# 2018_FDP_ACTIONNEUR.net
KiCad netlist of a schematic drawn in Altium Designer
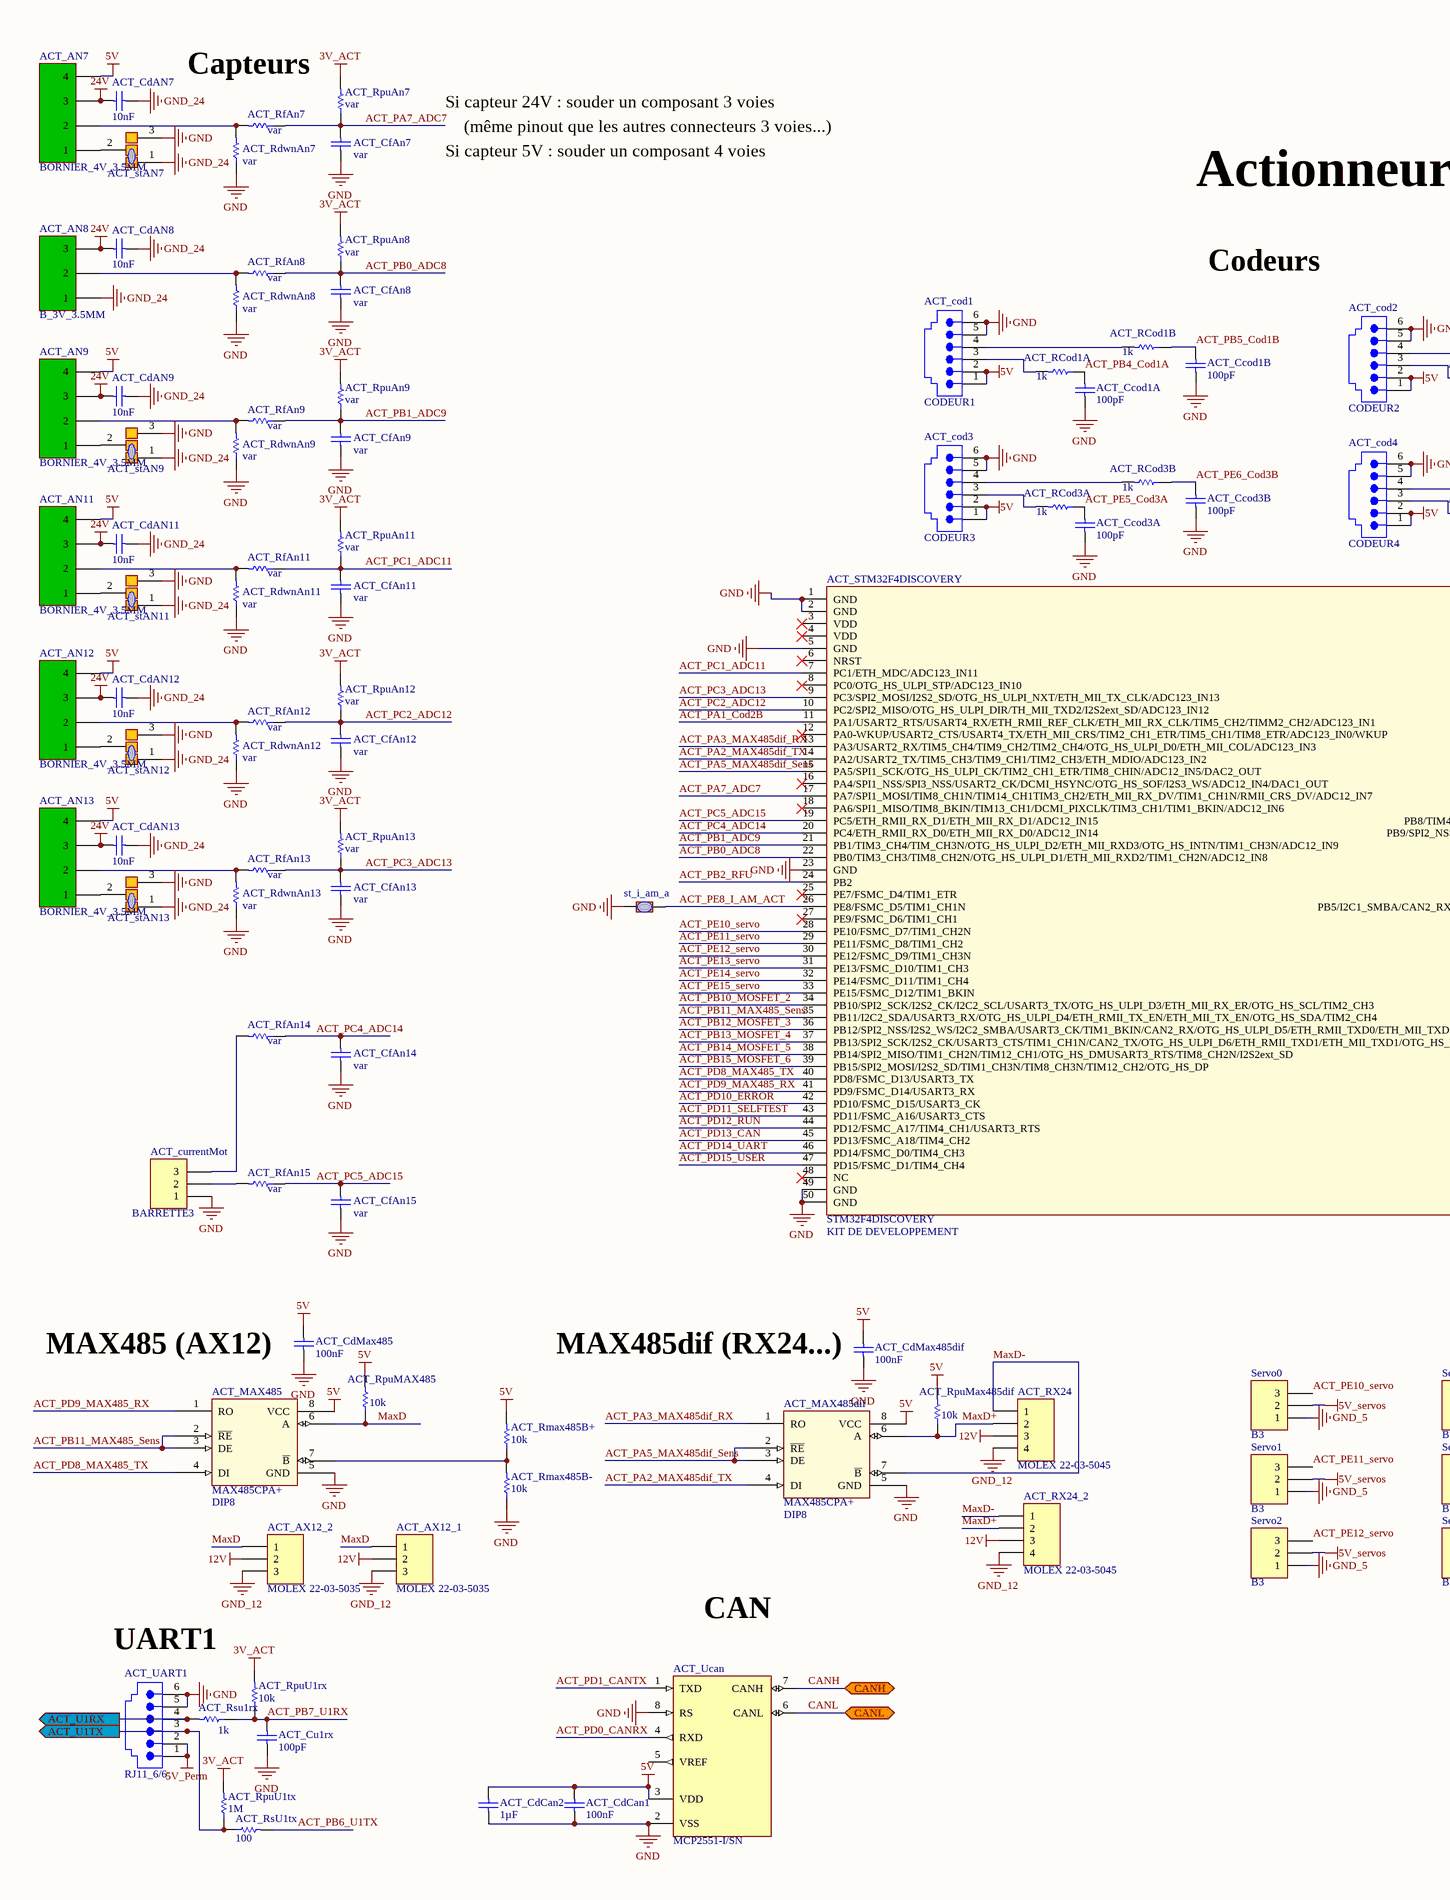
[diagram p0: 2018_FDP_ACTIONNEUR.SchDoc, left]
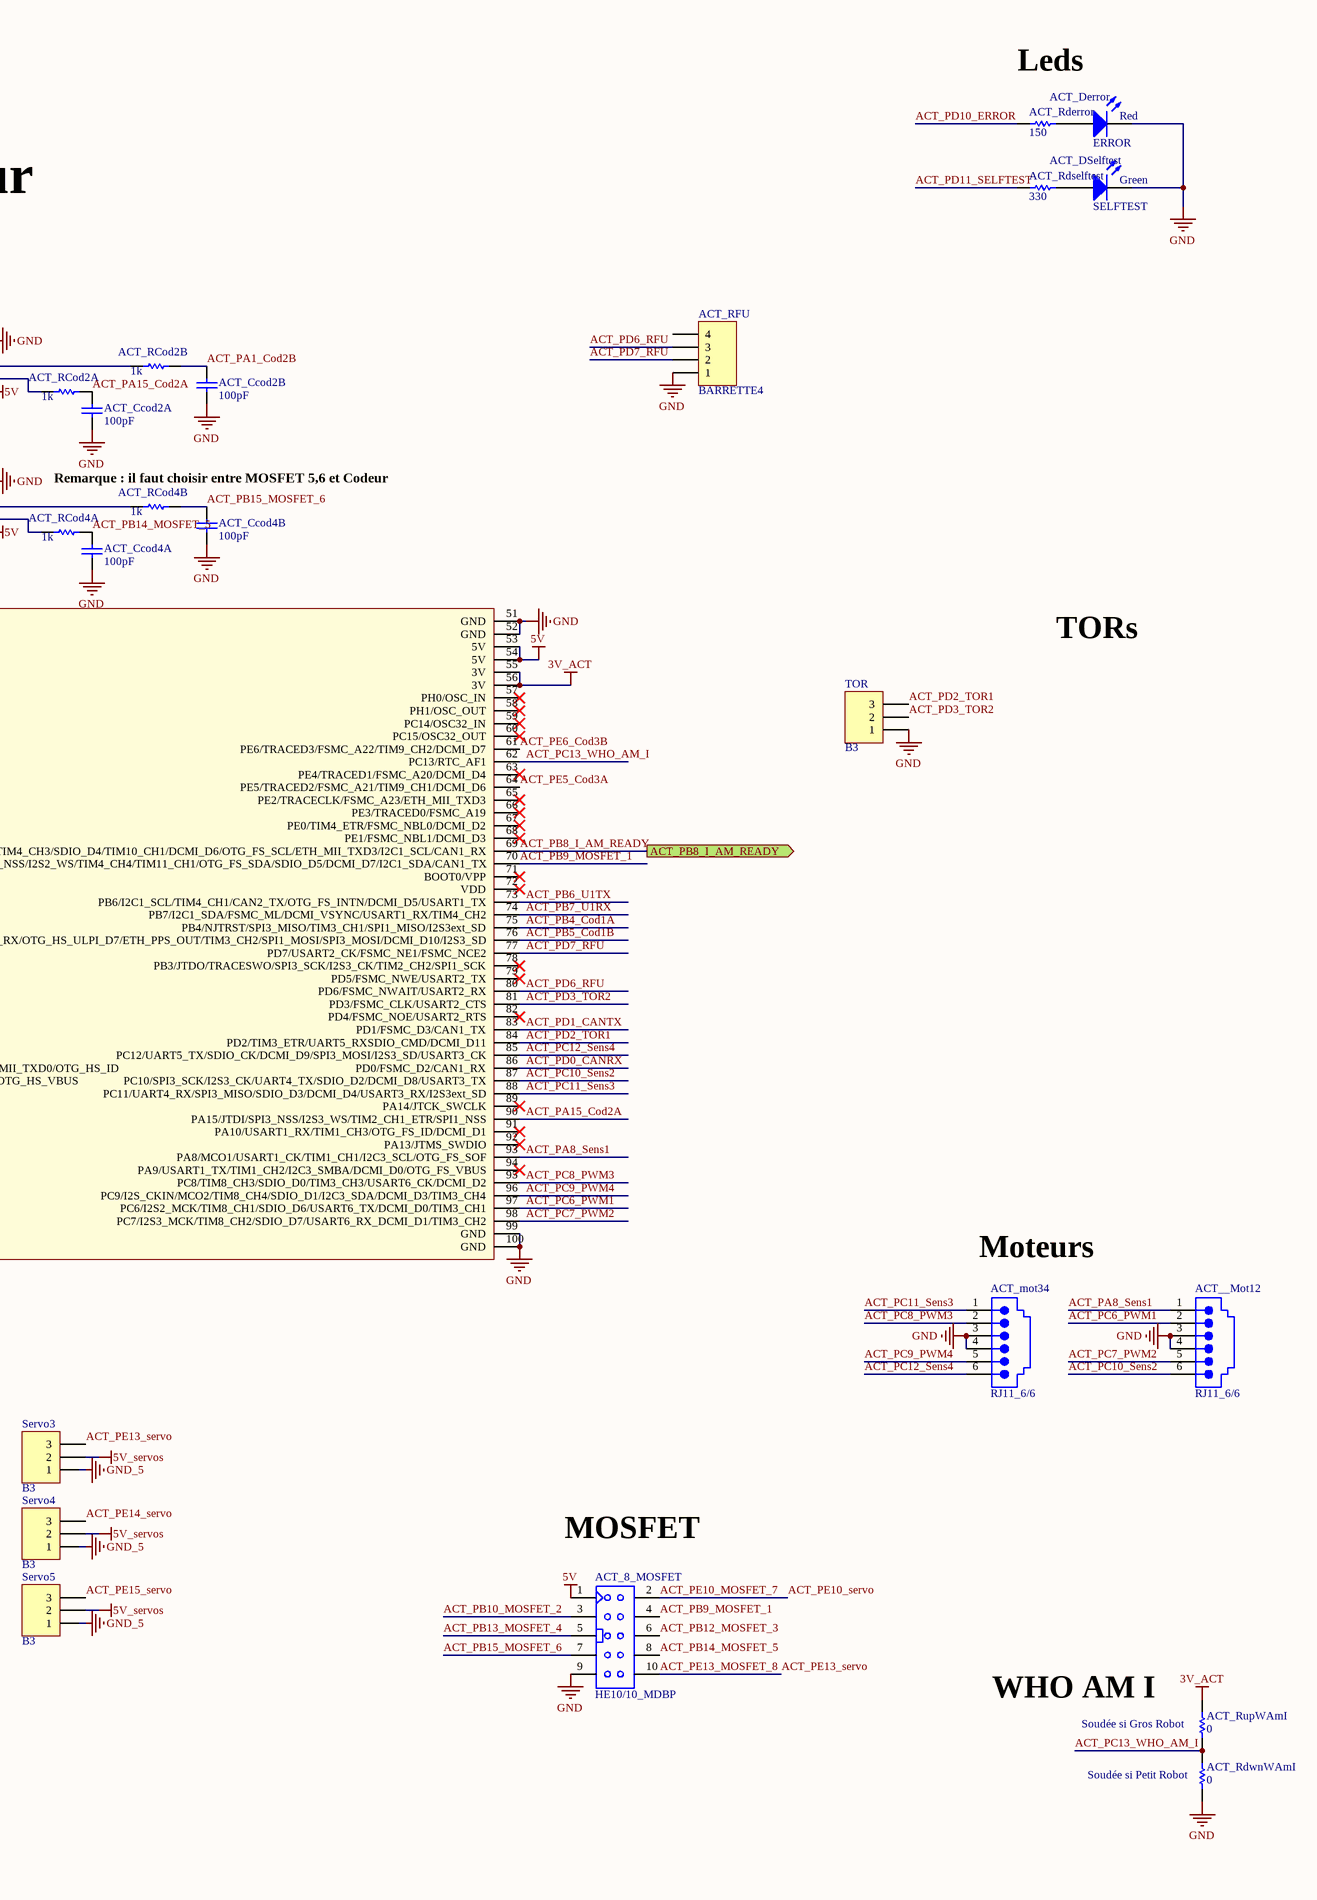
[diagram p1: 2018_FDP_ACTIONNEUR.SchDoc, right]

(export (version "E")
  (design (tool "Eeschema 10.0.6"))
  (components
    (comp (ref "ACT_8_MOSFET")
      (value "HE10/10_MALE_DROIT_BAS_PROFIL")
      (footprint "HE10/10_M_D_BP")
      (description "EMBASE HE10/10 MALE DROIT BAS PROFIL")
      (fields (field (name "TYPE") "HE10/10_MDBP"))
      (libsource (lib "connecteurs") (part "HE10/10_MALE_DROIT_BAS_PROFIL"))
    )
    (comp (ref "ACT_AN7")
      (value "BORNIER_4V_3.5MM")
      (footprint "BORNIER_4V_3.5MM")
      (libsource (lib "Connecteur") (part "BORNIER_4V_3.5MM"))
    )
    (comp (ref "ACT_AN8")
      (value "B_3V_3.5MM")
      (footprint "BORNIER_3V_3.5MM")
      (libsource (lib "Connecteur") (part "BORNIER_3V_3.5MM"))
    )
    (comp (ref "ACT_AN9")
      (value "BORNIER_4V_3.5MM")
      (footprint "BORNIER_4V_3.5MM")
      (libsource (lib "Connecteur") (part "BORNIER_4V_3.5MM"))
    )
    (comp (ref "ACT_AN11")
      (value "BORNIER_4V_3.5MM")
      (footprint "BORNIER_4V_3.5MM")
      (libsource (lib "Connecteur") (part "BORNIER_4V_3.5MM"))
    )
    (comp (ref "ACT_AN12")
      (value "BORNIER_4V_3.5MM")
      (footprint "BORNIER_4V_3.5MM")
      (libsource (lib "Connecteur") (part "BORNIER_4V_3.5MM"))
    )
    (comp (ref "ACT_AN13")
      (value "BORNIER_4V_3.5MM")
      (footprint "BORNIER_4V_3.5MM")
      (libsource (lib "Connecteur") (part "BORNIER_4V_3.5MM"))
    )
    (comp (ref "ACT_AX12_1")
      (value "MOLEX 22-03-5035")
      (footprint "MOLEX3_2.5MM")
      (description "Header, 3-Pin")
      (fields (field (name "PUBLISHER") "Altium Limited"))
      (libsource (lib "") (part "BARRETTE3_1"))
    )
    (comp (ref "ACT_AX12_2")
      (value "MOLEX 22-03-5035")
      (footprint "MOLEX3_2.5MM")
      (description "Header, 3-Pin")
      (fields (field (name "PUBLISHER") "Altium Limited"))
      (libsource (lib "") (part "BARRETTE3_1"))
    )
    (comp (ref "ACT_Ccod1A")
      (value "100pF")
      (footprint "C0805_N")
      (description "Capacitor")
      (fields (field (name "PUBLISHER") "Altium Limited"))
      (libsource (lib "_ROBOT") (part "Condensateur"))
    )
    (comp (ref "ACT_Ccod1B")
      (value "100pF")
      (footprint "C0805_N")
      (description "Capacitor")
      (fields (field (name "PUBLISHER") "Altium Limited"))
      (libsource (lib "_ROBOT") (part "Condensateur"))
    )
    (comp (ref "ACT_Ccod2A")
      (value "100pF")
      (footprint "C0805_N")
      (description "Capacitor")
      (fields (field (name "PUBLISHER") "Altium Limited"))
      (libsource (lib "_ROBOT") (part "Condensateur"))
    )
    (comp (ref "ACT_Ccod2B")
      (value "100pF")
      (footprint "C0805_N")
      (description "Capacitor")
      (fields (field (name "PUBLISHER") "Altium Limited"))
      (libsource (lib "_ROBOT") (part "Condensateur"))
    )
    (comp (ref "ACT_Ccod3A")
      (value "100pF")
      (footprint "C0805_N")
      (description "Capacitor")
      (fields (field (name "PUBLISHER") "Altium Limited"))
      (libsource (lib "_ROBOT") (part "Condensateur"))
    )
    (comp (ref "ACT_Ccod3B")
      (value "100pF")
      (footprint "C0805_N")
      (description "Capacitor")
      (fields (field (name "PUBLISHER") "Altium Limited"))
      (libsource (lib "_ROBOT") (part "Condensateur"))
    )
    (comp (ref "ACT_Ccod4A")
      (value "100pF")
      (footprint "C0805_N")
      (description "Capacitor")
      (fields (field (name "PUBLISHER") "Altium Limited"))
      (libsource (lib "_ROBOT") (part "Condensateur"))
    )
    (comp (ref "ACT_Ccod4B")
      (value "100pF")
      (footprint "C0805_N")
      (description "Capacitor")
      (fields (field (name "PUBLISHER") "Altium Limited"))
      (libsource (lib "_ROBOT") (part "Condensateur"))
    )
    (comp (ref "ACT_CdAN7")
      (value "10nF")
      (footprint "C0805_N")
      (description "Capacitor")
      (fields (field (name "PUBLISHER") "Altium Limited"))
      (libsource (lib "_ROBOT") (part "Condensateur"))
    )
    (comp (ref "ACT_CdAN8")
      (value "10nF")
      (footprint "C0805_N")
      (description "Capacitor")
      (fields (field (name "PUBLISHER") "Altium Limited"))
      (libsource (lib "_ROBOT") (part "Condensateur"))
    )
    (comp (ref "ACT_CdAN9")
      (value "10nF")
      (footprint "C0805_N")
      (description "Capacitor")
      (fields (field (name "PUBLISHER") "Altium Limited"))
      (libsource (lib "_ROBOT") (part "Condensateur"))
    )
    (comp (ref "ACT_CdAN11")
      (value "10nF")
      (footprint "C0805_N")
      (description "Capacitor")
      (fields (field (name "PUBLISHER") "Altium Limited"))
      (libsource (lib "_ROBOT") (part "Condensateur"))
    )
    (comp (ref "ACT_CdAN12")
      (value "10nF")
      (footprint "C0805_N")
      (description "Capacitor")
      (fields (field (name "PUBLISHER") "Altium Limited"))
      (libsource (lib "_ROBOT") (part "Condensateur"))
    )
    (comp (ref "ACT_CdAN13")
      (value "10nF")
      (footprint "C0805_N")
      (description "Capacitor")
      (fields (field (name "PUBLISHER") "Altium Limited"))
      (libsource (lib "_ROBOT") (part "Condensateur"))
    )
    (comp (ref "ACT_CdCan1")
      (value "100nF")
      (footprint "C0805_N")
      (description "Capacitor")
      (fields (field (name "PUBLISHER") "Altium Limited"))
      (libsource (lib "_ROBOT") (part "Condensateur"))
    )
    (comp (ref "ACT_CdCan2")
      (value "1µF")
      (footprint "C0805_N")
      (description "Capacitor")
      (fields (field (name "PUBLISHER") "Altium Limited"))
      (libsource (lib "_ROBOT") (part "Condensateur"))
    )
    (comp (ref "ACT_CdMax485")
      (value "100nF")
      (footprint "C0805_N")
      (description "Capacitor")
      (fields (field (name "PUBLISHER") "Altium Limited"))
      (libsource (lib "_ROBOT") (part "Condensateur"))
    )
    (comp (ref "ACT_CdMax485dif")
      (value "100nF")
      (footprint "C0805_N")
      (description "Capacitor")
      (fields (field (name "PUBLISHER") "Altium Limited"))
      (libsource (lib "_ROBOT") (part "Condensateur"))
    )
    (comp (ref "ACT_CfAn7")
      (value "var")
      (footprint "C0805_N")
      (description "Capacitor")
      (fields (field (name "PUBLISHER") "Altium Limited"))
      (libsource (lib "_ROBOT") (part "Condensateur"))
    )
    (comp (ref "ACT_CfAn8")
      (value "var")
      (footprint "C0805_N")
      (description "Capacitor")
      (fields (field (name "PUBLISHER") "Altium Limited"))
      (libsource (lib "_ROBOT") (part "Condensateur"))
    )
    (comp (ref "ACT_CfAn9")
      (value "var")
      (footprint "C0805_N")
      (description "Capacitor")
      (fields (field (name "PUBLISHER") "Altium Limited"))
      (libsource (lib "_ROBOT") (part "Condensateur"))
    )
    (comp (ref "ACT_CfAn11")
      (value "var")
      (footprint "C0805_N")
      (description "Capacitor")
      (fields (field (name "PUBLISHER") "Altium Limited"))
      (libsource (lib "_ROBOT") (part "Condensateur"))
    )
    (comp (ref "ACT_CfAn12")
      (value "var")
      (footprint "C0805_N")
      (description "Capacitor")
      (fields (field (name "PUBLISHER") "Altium Limited"))
      (libsource (lib "_ROBOT") (part "Condensateur"))
    )
    (comp (ref "ACT_CfAn13")
      (value "var")
      (footprint "C0805_N")
      (description "Capacitor")
      (fields (field (name "PUBLISHER") "Altium Limited"))
      (libsource (lib "_ROBOT") (part "Condensateur"))
    )
    (comp (ref "ACT_CfAn14")
      (value "var")
      (footprint "C0805_N")
      (description "Capacitor")
      (fields (field (name "PUBLISHER") "Altium Limited"))
      (libsource (lib "_ROBOT") (part "Condensateur"))
    )
    (comp (ref "ACT_CfAn15")
      (value "var")
      (footprint "C0805_N")
      (description "Capacitor")
      (fields (field (name "PUBLISHER") "Altium Limited"))
      (libsource (lib "_ROBOT") (part "Condensateur"))
    )
    (comp (ref "ACT_cod1")
      (value "CODEUR1")
      (footprint "RJ11_6/6 - droit")
      (description "Right Angle, Standard Profile, Offset Latch DECconnect, Flangeless PCB Jack")
      (fields (field (name "PUBLISHER") "Altium Limited"))
      (libsource (lib "miniprojet") (part "RJ11_6/6"))
    )
    (comp (ref "ACT_cod2")
      (value "CODEUR2")
      (footprint "RJ11_6/6 - droit")
      (description "Right Angle, Standard Profile, Offset Latch DECconnect, Flangeless PCB Jack")
      (fields (field (name "PUBLISHER") "Altium Limited"))
      (libsource (lib "miniprojet") (part "RJ11_6/6"))
    )
    (comp (ref "ACT_cod3")
      (value "CODEUR3")
      (footprint "RJ11_6/6 - droit")
      (description "Right Angle, Standard Profile, Offset Latch DECconnect, Flangeless PCB Jack")
      (fields (field (name "PUBLISHER") "Altium Limited"))
      (libsource (lib "miniprojet") (part "RJ11_6/6"))
    )
    (comp (ref "ACT_cod4")
      (value "CODEUR4")
      (footprint "RJ11_6/6 - droit")
      (description "Right Angle, Standard Profile, Offset Latch DECconnect, Flangeless PCB Jack")
      (fields (field (name "PUBLISHER") "Altium Limited"))
      (libsource (lib "miniprojet") (part "RJ11_6/6"))
    )
    (comp (ref "ACT_Cu1rx")
      (value "100pF")
      (footprint "C0805_N")
      (description "Capacitor")
      (fields (field (name "PUBLISHER") "Altium Limited"))
      (libsource (lib "_ROBOT") (part "Condensateur"))
    )
    (comp (ref "ACT_currentMot")
      (value "BARRETTE3")
      (footprint "HE14_3")
      (description "Header, 3-Pin")
      (fields (field (name "PUBLISHER") "Altium Limited"))
      (libsource (lib "Connecteur") (part "BARRETTE3"))
    )
    (comp (ref "ACT_Derror")
      (value "ERROR")
      (footprint "LED_0805")
      (description "Typical LED")
      (fields (field (name "PUBLISHER") "Altium Limited"))
      (libsource (lib "_ROBOT") (part "LED"))
    )
    (comp (ref "ACT_DSelftest")
      (value "SELFTEST")
      (footprint "LED_0805")
      (description "Typical LED")
      (fields (field (name "PUBLISHER") "Altium Limited"))
      (libsource (lib "_ROBOT") (part "LED"))
    )
    (comp (ref "ACT_MAX485")
      (value "MAX485CPA+_DIP8")
      (footprint "SO8_N")
      (description "EMETTEUR/RECEPTEUR FAIBLE PUISSANCE DE LIAISONS RS422/RS485 - DIP8")
      (fields (field (name "TYPE") "MAX485CPA+") (field (name "PACKAGE") "DIP8"))
      (libsource (lib "circuits integres") (part "MAX485CPA+_DIP8"))
    )
    (comp (ref "ACT_MAX485dif")
      (value "MAX485CPA+_DIP8")
      (footprint "SO8_N")
      (description "EMETTEUR/RECEPTEUR FAIBLE PUISSANCE DE LIAISONS RS422/RS485 - DIP8")
      (fields (field (name "TYPE") "MAX485CPA+") (field (name "PACKAGE") "DIP8"))
      (libsource (lib "circuits integres") (part "MAX485CPA+_DIP8"))
    )
    (comp (ref "ACT_mot34")
      (value "RJ11_6/6")
      (footprint "RJ11_6/6 - droit")
      (description "Right Angle, Standard Profile, Offset Latch DECconnect, Flangeless PCB Jack")
      (fields (field (name "PUBLISHER") "Altium Limited"))
      (libsource (lib "Connecteur") (part "RJ11_6/6"))
    )
    (comp (ref "ACT_RCod1A")
      (value "1k")
      (footprint "R1206_N")
      (description "Resistor")
      (fields (field (name "PUBLISHER") "Altium Limited"))
      (libsource (lib "_ROBOT") (part "Resistor"))
    )
    (comp (ref "ACT_RCod1B")
      (value "1k")
      (footprint "R1206_N")
      (description "Resistor")
      (fields (field (name "PUBLISHER") "Altium Limited"))
      (libsource (lib "_ROBOT") (part "Resistor"))
    )
    (comp (ref "ACT_RCod2A")
      (value "1k")
      (footprint "R1206_N")
      (description "Resistor")
      (fields (field (name "PUBLISHER") "Altium Limited"))
      (libsource (lib "_ROBOT") (part "Resistor"))
    )
    (comp (ref "ACT_RCod2B")
      (value "1k")
      (footprint "R1206_N")
      (description "Resistor")
      (fields (field (name "PUBLISHER") "Altium Limited"))
      (libsource (lib "_ROBOT") (part "Resistor"))
    )
    (comp (ref "ACT_RCod3A")
      (value "1k")
      (footprint "R1206_N")
      (description "Resistor")
      (fields (field (name "PUBLISHER") "Altium Limited"))
      (libsource (lib "_ROBOT") (part "Resistor"))
    )
    (comp (ref "ACT_RCod3B")
      (value "1k")
      (footprint "R1206_N")
      (description "Resistor")
      (fields (field (name "PUBLISHER") "Altium Limited"))
      (libsource (lib "_ROBOT") (part "Resistor"))
    )
    (comp (ref "ACT_RCod4A")
      (value "1k")
      (footprint "R1206_N")
      (description "Resistor")
      (fields (field (name "PUBLISHER") "Altium Limited"))
      (libsource (lib "_ROBOT") (part "Resistor"))
    )
    (comp (ref "ACT_RCod4B")
      (value "1k")
      (footprint "R1206_N")
      (description "Resistor")
      (fields (field (name "PUBLISHER") "Altium Limited"))
      (libsource (lib "_ROBOT") (part "Resistor"))
    )
    (comp (ref "ACT_Rderror")
      (value "150")
      (footprint "R1206_N")
      (description "Resistor")
      (fields (field (name "PUBLISHER") "Altium Limited"))
      (libsource (lib "_ROBOT") (part "Resistor"))
    )
    (comp (ref "ACT_Rdselftest")
      (value "330")
      (footprint "R1206_N")
      (description "Resistor")
      (fields (field (name "PUBLISHER") "Altium Limited"))
      (libsource (lib "_ROBOT") (part "Resistor"))
    )
    (comp (ref "ACT_RdwnAn7")
      (value "var")
      (footprint "R1206_N")
      (description "Resistor")
      (fields (field (name "PUBLISHER") "Altium Limited"))
      (libsource (lib "_ROBOT") (part "Resistor"))
    )
    (comp (ref "ACT_RdwnAn8")
      (value "var")
      (footprint "R1206_N")
      (description "Resistor")
      (fields (field (name "PUBLISHER") "Altium Limited"))
      (libsource (lib "_ROBOT") (part "Resistor"))
    )
    (comp (ref "ACT_RdwnAn9")
      (value "var")
      (footprint "R1206_N")
      (description "Resistor")
      (fields (field (name "PUBLISHER") "Altium Limited"))
      (libsource (lib "_ROBOT") (part "Resistor"))
    )
    (comp (ref "ACT_RdwnAn11")
      (value "var")
      (footprint "R1206_N")
      (description "Resistor")
      (fields (field (name "PUBLISHER") "Altium Limited"))
      (libsource (lib "_ROBOT") (part "Resistor"))
    )
    (comp (ref "ACT_RdwnAn12")
      (value "var")
      (footprint "R1206_N")
      (description "Resistor")
      (fields (field (name "PUBLISHER") "Altium Limited"))
      (libsource (lib "_ROBOT") (part "Resistor"))
    )
    (comp (ref "ACT_RdwnAn13")
      (value "var")
      (footprint "R1206_N")
      (description "Resistor")
      (fields (field (name "PUBLISHER") "Altium Limited"))
      (libsource (lib "_ROBOT") (part "Resistor"))
    )
    (comp (ref "ACT_RdwnWAmI")
      (value "0")
      (footprint "R1206_N")
      (description "Resistor")
      (fields (field (name "PUBLISHER") "Altium Limited"))
      (libsource (lib "_ROBOT") (part "Resistor"))
    )
    (comp (ref "ACT_RfAn7")
      (value "var")
      (footprint "R1206_N")
      (description "Resistor")
      (fields (field (name "PUBLISHER") "Altium Limited"))
      (libsource (lib "_ROBOT") (part "Resistor"))
    )
    (comp (ref "ACT_RfAn8")
      (value "var")
      (footprint "R1206_N")
      (description "Resistor")
      (fields (field (name "PUBLISHER") "Altium Limited"))
      (libsource (lib "_ROBOT") (part "Resistor"))
    )
    (comp (ref "ACT_RfAn9")
      (value "var")
      (footprint "R1206_N")
      (description "Resistor")
      (fields (field (name "PUBLISHER") "Altium Limited"))
      (libsource (lib "_ROBOT") (part "Resistor"))
    )
    (comp (ref "ACT_RfAn11")
      (value "var")
      (footprint "R1206_N")
      (description "Resistor")
      (fields (field (name "PUBLISHER") "Altium Limited"))
      (libsource (lib "_ROBOT") (part "Resistor"))
    )
    (comp (ref "ACT_RfAn12")
      (value "var")
      (footprint "R1206_N")
      (description "Resistor")
      (fields (field (name "PUBLISHER") "Altium Limited"))
      (libsource (lib "_ROBOT") (part "Resistor"))
    )
    (comp (ref "ACT_RfAn13")
      (value "var")
      (footprint "R1206_N")
      (description "Resistor")
      (fields (field (name "PUBLISHER") "Altium Limited"))
      (libsource (lib "_ROBOT") (part "Resistor"))
    )
    (comp (ref "ACT_RfAn14")
      (value "var")
      (footprint "R1206_N")
      (description "Resistor")
      (fields (field (name "PUBLISHER") "Altium Limited"))
      (libsource (lib "_ROBOT") (part "Resistor"))
    )
    (comp (ref "ACT_RfAn15")
      (value "var")
      (footprint "R1206_N")
      (description "Resistor")
      (fields (field (name "PUBLISHER") "Altium Limited"))
      (libsource (lib "_ROBOT") (part "Resistor"))
    )
    (comp (ref "ACT_RFU")
      (value "BARRETTE4")
      (footprint "HE14_4")
      (description "Header, 4-Pin")
      (fields (field (name "PUBLISHER") "Altium Limited"))
      (libsource (lib "") (part "BARRETTE4_1"))
    )
    (comp (ref "ACT_Rmax485B+")
      (value "10k")
      (footprint "R1206_N")
      (description "Resistor")
      (fields (field (name "PUBLISHER") "Altium Limited"))
      (libsource (lib "_ROBOT") (part "Resistor"))
    )
    (comp (ref "ACT_Rmax485B-")
      (value "10k")
      (footprint "R1206_N")
      (description "Resistor")
      (fields (field (name "PUBLISHER") "Altium Limited"))
      (libsource (lib "_ROBOT") (part "Resistor"))
    )
    (comp (ref "ACT_RpuAn7")
      (value "var")
      (footprint "R1206_N")
      (description "Resistor")
      (fields (field (name "PUBLISHER") "Altium Limited"))
      (libsource (lib "_ROBOT") (part "Resistor"))
    )
    (comp (ref "ACT_RpuAn8")
      (value "var")
      (footprint "R1206_N")
      (description "Resistor")
      (fields (field (name "PUBLISHER") "Altium Limited"))
      (libsource (lib "_ROBOT") (part "Resistor"))
    )
    (comp (ref "ACT_RpuAn9")
      (value "var")
      (footprint "R1206_N")
      (description "Resistor")
      (fields (field (name "PUBLISHER") "Altium Limited"))
      (libsource (lib "_ROBOT") (part "Resistor"))
    )
    (comp (ref "ACT_RpuAn11")
      (value "var")
      (footprint "R1206_N")
      (description "Resistor")
      (fields (field (name "PUBLISHER") "Altium Limited"))
      (libsource (lib "_ROBOT") (part "Resistor"))
    )
    (comp (ref "ACT_RpuAn12")
      (value "var")
      (footprint "R1206_N")
      (description "Resistor")
      (fields (field (name "PUBLISHER") "Altium Limited"))
      (libsource (lib "_ROBOT") (part "Resistor"))
    )
    (comp (ref "ACT_RpuAn13")
      (value "var")
      (footprint "R1206_N")
      (description "Resistor")
      (fields (field (name "PUBLISHER") "Altium Limited"))
      (libsource (lib "_ROBOT") (part "Resistor"))
    )
    (comp (ref "ACT_RpuMAX485")
      (value "10k")
      (footprint "R1206_N")
      (description "Resistor")
      (fields (field (name "PUBLISHER") "Altium Limited"))
      (libsource (lib "_ROBOT") (part "Resistor"))
    )
    (comp (ref "ACT_RpuMax485dif")
      (value "10k")
      (footprint "R1206_N")
      (description "Resistor")
      (fields (field (name "PUBLISHER") "Altium Limited"))
      (libsource (lib "_ROBOT") (part "Resistor"))
    )
    (comp (ref "ACT_RpuU1rx")
      (value "10k")
      (footprint "R1206_N")
      (description "Resistor")
      (fields (field (name "PUBLISHER") "Altium Limited"))
      (libsource (lib "_ROBOT") (part "Resistor"))
    )
    (comp (ref "ACT_RpuU1tx")
      (value "1M")
      (footprint "R1206_N")
      (description "Resistor")
      (fields (field (name "PUBLISHER") "Altium Limited"))
      (libsource (lib "_ROBOT") (part "Resistor"))
    )
    (comp (ref "ACT_Rsu1rx")
      (value "1k")
      (footprint "R1206_N")
      (description "Resistor")
      (fields (field (name "PUBLISHER") "Altium Limited"))
      (libsource (lib "_ROBOT") (part "Resistor"))
    )
    (comp (ref "ACT_RsU1tx")
      (value "100")
      (footprint "R1206_N")
      (description "Resistor")
      (fields (field (name "PUBLISHER") "Altium Limited"))
      (libsource (lib "_ROBOT") (part "Resistor"))
    )
    (comp (ref "ACT_RupWAmI")
      (value "0")
      (footprint "R1206_N")
      (description "Resistor")
      (fields (field (name "PUBLISHER") "Altium Limited"))
      (libsource (lib "_ROBOT") (part "Resistor"))
    )
    (comp (ref "ACT_RX24")
      (value "MOLEX 22-03-5045")
      (footprint "MOLEX4_2.5MM")
      (description "Header, 4-Pin")
      (fields (field (name "PUBLISHER") "Altium Limited"))
      (libsource (lib "Connecteur") (part "BARRETTE4"))
    )
    (comp (ref "ACT_RX24_2")
      (value "MOLEX 22-03-5045")
      (footprint "MOLEX4_2.5MM")
      (description "Header, 4-Pin")
      (fields (field (name "PUBLISHER") "Altium Limited"))
      (libsource (lib "Connecteur") (part "BARRETTE4"))
    )
    (comp (ref "ACT_stAN7")
      (value "strap")
      (footprint "Goutte Strap_3")
      (description "Goutte Strap_3")
      (fields (field (name "PUBLISHER") "Damien Guitton"))
      (libsource (lib "DG_Connecteur") (part "Goutte Strap_3"))
    )
    (comp (ref "ACT_stAN9")
      (value "strap")
      (footprint "Goutte Strap_3")
      (description "Goutte Strap_3")
      (fields (field (name "PUBLISHER") "Damien Guitton"))
      (libsource (lib "DG_Connecteur") (part "Goutte Strap_3"))
    )
    (comp (ref "ACT_stAN11")
      (value "strap")
      (footprint "Goutte Strap_3")
      (description "Goutte Strap_3")
      (fields (field (name "PUBLISHER") "Damien Guitton"))
      (libsource (lib "DG_Connecteur") (part "Goutte Strap_3"))
    )
    (comp (ref "ACT_stAN12")
      (value "strap")
      (footprint "Goutte Strap_3")
      (description "Goutte Strap_3")
      (fields (field (name "PUBLISHER") "Damien Guitton"))
      (libsource (lib "DG_Connecteur") (part "Goutte Strap_3"))
    )
    (comp (ref "ACT_stAN13")
      (value "strap")
      (footprint "Goutte Strap_3")
      (description "Goutte Strap_3")
      (fields (field (name "PUBLISHER") "Damien Guitton"))
      (libsource (lib "DG_Connecteur") (part "Goutte Strap_3"))
    )
    (comp (ref "ACT_STM32F4DISCOVERY")
      (value "STM32F4DISCOVERY")
      (footprint "STM32_F4DISCOVERY")
      (description "KIT DE DEVELOPPEMENT POUR MICROCONTROLEUR STM32F407VGT6")
      (fields (field (name "TYPE") "KIT DE DEVELOPPEMENT"))
      (libsource (lib "circuits integres") (part "STM32F4DISCOVERY"))
    )
    (comp (ref "ACT_UART1")
      (value "RJ11_6/6")
      (footprint "RJ11_6/6 - droit")
      (description "Right Angle, Standard Profile, Offset Latch DECconnect, Flangeless PCB Jack")
      (fields (field (name "PUBLISHER") "Altium Limited"))
      (libsource (lib "Connecteur") (part "RJ11_6/6"))
    )
    (comp (ref "ACT_Ucan")
      (value "MCP2551-I/SN")
      (footprint "SO8_N")
      (description "High-Speed CAN Transceiver, 8-Pin SOIC, Industrial Temperature")
      (fields (field (name "PUBLISHER") "Damien Guitton"))
      (libsource (lib "Circuit intégré") (part "MCP2551-I/SN"))
    )
    (comp (ref "ACT__Mot12")
      (value "RJ11_6/6")
      (footprint "RJ11_6/6 - droit")
      (description "Right Angle, Standard Profile, Offset Latch DECconnect, Flangeless PCB Jack")
      (fields (field (name "PUBLISHER") "Altium Limited"))
      (libsource (lib "Connecteur") (part "RJ11_6/6"))
    )
    (comp (ref "Servo0")
      (value "B3")
      (footprint "HE14_3")
      (description "Header, 3-Pin")
      (fields (field (name "PUBLISHER") "Altium Limited"))
      (libsource (lib "Connecteur") (part "BARRETTE3"))
    )
    (comp (ref "Servo1")
      (value "B3")
      (footprint "HE14_3")
      (description "Header, 3-Pin")
      (fields (field (name "PUBLISHER") "Altium Limited"))
      (libsource (lib "Connecteur") (part "BARRETTE3"))
    )
    (comp (ref "Servo2")
      (value "B3")
      (footprint "HE14_3")
      (description "Header, 3-Pin")
      (fields (field (name "PUBLISHER") "Altium Limited"))
      (libsource (lib "Connecteur") (part "BARRETTE3"))
    )
    (comp (ref "Servo3")
      (value "B3")
      (footprint "HE14_3")
      (description "Header, 3-Pin")
      (fields (field (name "PUBLISHER") "Altium Limited"))
      (libsource (lib "Connecteur") (part "BARRETTE3"))
    )
    (comp (ref "Servo4")
      (value "B3")
      (footprint "HE14_3")
      (description "Header, 3-Pin")
      (fields (field (name "PUBLISHER") "Altium Limited"))
      (libsource (lib "Connecteur") (part "BARRETTE3"))
    )
    (comp (ref "Servo5")
      (value "B3")
      (footprint "HE14_3")
      (description "Header, 3-Pin")
      (fields (field (name "PUBLISHER") "Altium Limited"))
      (libsource (lib "Connecteur") (part "BARRETTE3"))
    )
    (comp (ref "st_i_am_a")
      (value "Goutte Strap_2")
      (footprint "Goutte Strap_2 Pads_Clearance 0.254mm")
      (fields (field (name "PUBLISHER") "Damien Guitton"))
      (libsource (lib "DG_Connecteur") (part "Goutte Strap_2"))
    )
    (comp (ref "TOR")
      (value "B3")
      (footprint "HE14_3")
      (description "Header, 3-Pin")
      (fields (field (name "PUBLISHER") "Altium Limited"))
      (libsource (lib "Connecteur") (part "BARRETTE3"))
    )
  )
  (nets
    (net (code "1") (name "/ACT_PA1_Cod2B") (class "Default")
      (node (ref "ACT_Ccod2B") (pin "2") (pinfunction "2_2") (pintype "passive"))
      (node (ref "ACT_RCod2B") (pin "1") (pinfunction "1_1") (pintype "passive"))
      (node (ref "ACT_STM32F4DISCOVERY") (pin "11") (pinfunction "PA1/USART2_RTS/USART4_RX/ETH_RMII_REF_CLK/ETH_MII_RX_CLK/TIM5_CH2/TIMM2_CH2/ADC123_IN1_11") (pintype "passive"))
    )
    (net (code "2") (name "/ACT_PA2_MAX485dif_TX") (class "Default")
      (node (ref "ACT_MAX485dif") (pin "4") (pinfunction "DI_4") (pintype "input"))
      (node (ref "ACT_STM32F4DISCOVERY") (pin "14") (pinfunction "PA2/USART2_TX/TIM5_CH3/TIM9_CH1/TIM2_CH3/ETH_MDIO/ADC123_IN2_14") (pintype "passive"))
    )
    (net (code "3") (name "/ACT_PA3_MAX485dif_RX") (class "Default")
      (node (ref "ACT_MAX485dif") (pin "1") (pinfunction "RO_1") (pintype "tri_state"))
      (node (ref "ACT_STM32F4DISCOVERY") (pin "13") (pinfunction "PA3/USART2_RX/TIM5_CH4/TIM9_CH2/TIM2_CH4/OTG_HS_ULPI_D0/ETH_MII_COL/ADC123_IN3_13") (pintype "passive"))
    )
    (net (code "4") (name "/ACT_PA5_MAX485dif_Sens") (class "Default")
      (node (ref "ACT_MAX485dif") (pin "2") (pinfunction "~{RE}_2") (pintype "input"))
      (node (ref "ACT_MAX485dif") (pin "3") (pinfunction "DE_3") (pintype "input"))
      (node (ref "ACT_STM32F4DISCOVERY") (pin "15") (pinfunction "PA5/SPI1_SCK/OTG_HS_ULPI_CK/TIM2_CH1_ETR/TIM8_CHIN/ADC12_IN5/DAC2_OUT_15") (pintype "passive"))
    )
    (net (code "5") (name "/ACT_PA7_ADC7") (class "Default")
      (node (ref "ACT_CfAn7") (pin "2") (pinfunction "2_2") (pintype "passive"))
      (node (ref "ACT_RfAn7") (pin "1") (pinfunction "1_1") (pintype "passive"))
      (node (ref "ACT_RpuAn7") (pin "1") (pinfunction "1_1") (pintype "passive"))
      (node (ref "ACT_STM32F4DISCOVERY") (pin "17") (pinfunction "PA7/SPI1_MOSI/TIM8_CH1N/TIM14_CH1TIM3_CH2/ETH_MII_RX_DV/TIM1_CH1N/RMII_CRS_DV/ADC12_IN7_17") (pintype "passive"))
    )
    (net (code "6") (name "/ACT_PA8_Sens1") (class "Default")
      (node (ref "ACT_STM32F4DISCOVERY") (pin "93") (pinfunction "PA8/MCO1/USART1_CK/TIM1_CH1/I2C3_SCL/OTG_FS_SOF_93") (pintype "passive"))
      (node (ref "ACT__Mot12") (pin "1") (pinfunction "1_1") (pintype "passive"))
    )
    (net (code "7") (name "/ACT_PA15_Cod2A") (class "Default")
      (node (ref "ACT_Ccod2A") (pin "2") (pinfunction "2_2") (pintype "passive"))
      (node (ref "ACT_RCod2A") (pin "1") (pinfunction "1_1") (pintype "passive"))
      (node (ref "ACT_STM32F4DISCOVERY") (pin "90") (pinfunction "PA15/JTDI/SPI3_NSS/I2S3_WS/TIM2_CH1_ETR/SPI1_NSS_90") (pintype "passive"))
    )
    (net (code "8") (name "/ACT_PB0_ADC8") (class "Default")
      (node (ref "ACT_CfAn8") (pin "2") (pinfunction "2_2") (pintype "passive"))
      (node (ref "ACT_RfAn8") (pin "1") (pinfunction "1_1") (pintype "passive"))
      (node (ref "ACT_RpuAn8") (pin "1") (pinfunction "1_1") (pintype "passive"))
      (node (ref "ACT_STM32F4DISCOVERY") (pin "22") (pinfunction "PB0/TIM3_CH3/TIM8_CH2N/OTG_HS_ULPI_D1/ETH_MII_RXD2/TIM1_CH2N/ADC12_IN8_22") (pintype "passive"))
    )
    (net (code "9") (name "/ACT_PB1_ADC9") (class "Default")
      (node (ref "ACT_CfAn9") (pin "2") (pinfunction "2_2") (pintype "passive"))
      (node (ref "ACT_RfAn9") (pin "1") (pinfunction "1_1") (pintype "passive"))
      (node (ref "ACT_RpuAn9") (pin "1") (pinfunction "1_1") (pintype "passive"))
      (node (ref "ACT_STM32F4DISCOVERY") (pin "21") (pinfunction "PB1/TIM3_CH4/TIM_CH3N/OTG_HS_ULPI_D2/ETH_MII_RXD3/OTG_HS_INTN/TIM1_CH3N/ADC12_IN9_21") (pintype "passive"))
    )
    (net (code "10") (name "/ACT_PB2_RFU") (class "Default")
      (node (ref "ACT_STM32F4DISCOVERY") (pin "24") (pinfunction "PB2_24") (pintype "passive"))
    )
    (net (code "11") (name "/ACT_PB4_Cod1A") (class "Default")
      (node (ref "ACT_Ccod1A") (pin "2") (pinfunction "2_2") (pintype "passive"))
      (node (ref "ACT_RCod1A") (pin "1") (pinfunction "1_1") (pintype "passive"))
      (node (ref "ACT_STM32F4DISCOVERY") (pin "75") (pinfunction "PB4/NJTRST/SPI3_MISO/TIM3_CH1/SPI1_MISO/I2S3ext_SD_75") (pintype "passive"))
    )
    (net (code "12") (name "/ACT_PB5_Cod1B") (class "Default")
      (node (ref "ACT_Ccod1B") (pin "2") (pinfunction "2_2") (pintype "passive"))
      (node (ref "ACT_RCod1B") (pin "1") (pinfunction "1_1") (pintype "passive"))
      (node (ref "ACT_STM32F4DISCOVERY") (pin "76") (pinfunction "PB5/I2C1_SMBA/CAN2_RX/OTG_HS_ULPI_D7/ETH_PPS_OUT/TIM3_CH2/SPI1_MOSI/SPI3_MOSI/DCMI_D10/I2S3_SD_76") (pintype "passive"))
    )
    (net (code "13") (name "/ACT_PB6_U1TX") (class "Default")
      (node (ref "ACT_RsU1tx") (pin "2") (pinfunction "2_2") (pintype "passive"))
      (node (ref "ACT_STM32F4DISCOVERY") (pin "73") (pinfunction "PB6/I2C1_SCL/TIM4_CH1/CAN2_TX/OTG_FS_INTN/DCMI_D5/USART1_TX_73") (pintype "passive"))
    )
    (net (code "14") (name "/ACT_PB7_U1RX") (class "Default")
      (node (ref "ACT_Cu1rx") (pin "2") (pinfunction "2_2") (pintype "passive"))
      (node (ref "ACT_RpuU1rx") (pin "1") (pinfunction "1_1") (pintype "passive"))
      (node (ref "ACT_Rsu1rx") (pin "1") (pinfunction "1_1") (pintype "passive"))
      (node (ref "ACT_STM32F4DISCOVERY") (pin "74") (pinfunction "PB7/I2C1_SDA/FSMC_ML/DCMI_VSYNC/USART1_RX/TIM4_CH2_74") (pintype "passive"))
    )
    (net (code "15") (name "/ACT_PB8_I_AM_READY") (class "Default")
      (node (ref "ACT_STM32F4DISCOVERY") (pin "69") (pinfunction "PB8/TIM4_CH3/SDIO_D4/TIM10_CH1/DCMI_D6/OTG_FS_SCL/ETH_MII_TXD3/I2C1_SCL/CAN1_RX_69") (pintype "passive"))
    )
    (net (code "16") (name "/ACT_PB9_MOSFET_1") (class "Default")
      (node (ref "ACT_8_MOSFET") (pin "4") (pinfunction "4_4") (pintype "passive"))
      (node (ref "ACT_STM32F4DISCOVERY") (pin "70") (pinfunction "PB9/SPI2_NSS/I2S2_WS/TIM4_CH4/TIM11_CH1/OTG_FS_SDA/SDIO_D5/DCMI_D7/I2C1_SDA/CAN1_TX_70") (pintype "passive"))
    )
    (net (code "17") (name "/ACT_PB10_MOSFET_2") (class "Default")
      (node (ref "ACT_8_MOSFET") (pin "3") (pinfunction "3_3") (pintype "passive"))
      (node (ref "ACT_STM32F4DISCOVERY") (pin "34") (pinfunction "PB10/SPI2_SCK/I2S2_CK/I2C2_SCL/USART3_TX/OTG_HS_ULPI_D3/ETH_MII_RX_ER/OTG_HS_SCL/TIM2_CH3_34") (pintype "passive"))
    )
    (net (code "18") (name "/ACT_PB11_MAX485_Sens") (class "Default")
      (node (ref "ACT_MAX485") (pin "2") (pinfunction "~{RE}_2") (pintype "input"))
      (node (ref "ACT_MAX485") (pin "3") (pinfunction "DE_3") (pintype "input"))
      (node (ref "ACT_STM32F4DISCOVERY") (pin "35") (pinfunction "PB11/I2C2_SDA/USART3_RX/OTG_HS_ULPI_D4/ETH_RMII_TX_EN/ETH_MII_TX_EN/OTG_HS_SDA/TIM2_CH4_35") (pintype "passive"))
    )
    (net (code "19") (name "/ACT_PB12_MOSFET_3") (class "Default")
      (node (ref "ACT_8_MOSFET") (pin "6") (pinfunction "6_6") (pintype "passive"))
      (node (ref "ACT_STM32F4DISCOVERY") (pin "36") (pinfunction "PB12/SPI2_NSS/I2S2_WS/I2C2_SMBA/USART3_CK/TIM1_BKIN/CAN2_RX/OTG_HS_ULPI_D5/ETH_RMII_TXD0/ETH_MII_TXD0/OTG_HS_ID_36") (pintype "passive"))
    )
    (net (code "20") (name "/ACT_PB13_MOSFET_4") (class "Default")
      (node (ref "ACT_8_MOSFET") (pin "5") (pinfunction "5_5") (pintype "passive"))
      (node (ref "ACT_STM32F4DISCOVERY") (pin "37") (pinfunction "PB13/SPI2_SCK/I2S2_CK/USART3_CTS/TIM1_CH1N/CAN2_TX/OTG_HS_ULPI_D6/ETH_RMII_TXD1/ETH_MII_TXD1/OTG_HS_VBUS_37") (pintype "passive"))
    )
    (net (code "21") (name "/ACT_PB14_MOSFET_5") (class "Default")
      (node (ref "ACT_8_MOSFET") (pin "8") (pinfunction "8_8") (pintype "passive"))
      (node (ref "ACT_Ccod4A") (pin "2") (pinfunction "2_2") (pintype "passive"))
      (node (ref "ACT_RCod4A") (pin "1") (pinfunction "1_1") (pintype "passive"))
      (node (ref "ACT_STM32F4DISCOVERY") (pin "38") (pinfunction "PB14/SPI2_MISO/TIM1_CH2N/TIM12_CH1/OTG_HS_DMUSART3_RTS/TIM8_CH2N/I2S2ext_SD_38") (pintype "passive"))
    )
    (net (code "22") (name "/ACT_PB15_MOSFET_6") (class "Default")
      (node (ref "ACT_8_MOSFET") (pin "7") (pinfunction "7_7") (pintype "passive"))
      (node (ref "ACT_Ccod4B") (pin "2") (pinfunction "2_2") (pintype "passive"))
      (node (ref "ACT_RCod4B") (pin "1") (pinfunction "1_1") (pintype "passive"))
      (node (ref "ACT_STM32F4DISCOVERY") (pin "39") (pinfunction "PB15/SPI2_MOSI/I2S2_SD/TIM1_CH3N/TIM8_CH3N/TIM12_CH2/OTG_HS_DP_39") (pintype "passive"))
    )
    (net (code "23") (name "/ACT_PC1_ADC11") (class "Default")
      (node (ref "ACT_CfAn11") (pin "2") (pinfunction "2_2") (pintype "passive"))
      (node (ref "ACT_RfAn11") (pin "1") (pinfunction "1_1") (pintype "passive"))
      (node (ref "ACT_RpuAn11") (pin "1") (pinfunction "1_1") (pintype "passive"))
      (node (ref "ACT_STM32F4DISCOVERY") (pin "7") (pinfunction "PC1/ETH_MDC/ADC123_IN11_7") (pintype "passive"))
    )
    (net (code "24") (name "/ACT_PC2_ADC12") (class "Default")
      (node (ref "ACT_CfAn12") (pin "2") (pinfunction "2_2") (pintype "passive"))
      (node (ref "ACT_RfAn12") (pin "1") (pinfunction "1_1") (pintype "passive"))
      (node (ref "ACT_RpuAn12") (pin "1") (pinfunction "1_1") (pintype "passive"))
      (node (ref "ACT_STM32F4DISCOVERY") (pin "10") (pinfunction "PC2/SPI2_MISO/OTG_HS_ULPI_DIR/TH_MII_TXD2/I2S2ext_SD/ADC123_IN12_10") (pintype "passive"))
    )
    (net (code "25") (name "/ACT_PC3_ADC13") (class "Default")
      (node (ref "ACT_CfAn13") (pin "2") (pinfunction "2_2") (pintype "passive"))
      (node (ref "ACT_RfAn13") (pin "1") (pinfunction "1_1") (pintype "passive"))
      (node (ref "ACT_RpuAn13") (pin "1") (pinfunction "1_1") (pintype "passive"))
      (node (ref "ACT_STM32F4DISCOVERY") (pin "9") (pinfunction "PC3/SPI2_MOSI/I2S2_SD/OTG_HS_ULPI_NXT/ETH_MII_TX_CLK/ADC123_IN13_9") (pintype "passive"))
    )
    (net (code "26") (name "/ACT_PC4_ADC14") (class "Default")
      (node (ref "ACT_CfAn14") (pin "2") (pinfunction "2_2") (pintype "passive"))
      (node (ref "ACT_RfAn14") (pin "1") (pinfunction "1_1") (pintype "passive"))
      (node (ref "ACT_STM32F4DISCOVERY") (pin "20") (pinfunction "PC4/ETH_RMII_RX_D0/ETH_MII_RX_D0/ADC12_IN14_20") (pintype "passive"))
    )
    (net (code "27") (name "/ACT_PC5_ADC15") (class "Default")
      (node (ref "ACT_CfAn15") (pin "2") (pinfunction "2_2") (pintype "passive"))
      (node (ref "ACT_RfAn15") (pin "1") (pinfunction "1_1") (pintype "passive"))
      (node (ref "ACT_STM32F4DISCOVERY") (pin "19") (pinfunction "PC5/ETH_RMII_RX_D1/ETH_MII_RX_D1/ADC12_IN15_19") (pintype "passive"))
    )
    (net (code "28") (name "/ACT_PC6_PWM1") (class "Default")
      (node (ref "ACT_STM32F4DISCOVERY") (pin "97") (pinfunction "PC6/I2S2_MCK/TIM8_CH1/SDIO_D6/USART6_TX/DCMI_D0/TIM3_CH1_97") (pintype "passive"))
      (node (ref "ACT__Mot12") (pin "2") (pinfunction "2_2") (pintype "passive"))
    )
    (net (code "29") (name "/ACT_PC7_PWM2") (class "Default")
      (node (ref "ACT_STM32F4DISCOVERY") (pin "98") (pinfunction "PC7/I2S3_MCK/TIM8_CH2/SDIO_D7/USART6_RX_DCMI_D1/TIM3_CH2_98") (pintype "passive"))
      (node (ref "ACT__Mot12") (pin "5") (pinfunction "5_5") (pintype "passive"))
    )
    (net (code "30") (name "/ACT_PC8_PWM3") (class "Default")
      (node (ref "ACT_STM32F4DISCOVERY") (pin "95") (pinfunction "PC8/TIM8_CH3/SDIO_D0/TIM3_CH3/USART6_CK/DCMI_D2_95") (pintype "passive"))
      (node (ref "ACT_mot34") (pin "2") (pinfunction "2_2") (pintype "passive"))
    )
    (net (code "31") (name "/ACT_PC9_PWM4") (class "Default")
      (node (ref "ACT_STM32F4DISCOVERY") (pin "96") (pinfunction "PC9/I2S_CKIN/MCO2/TIM8_CH4/SDIO_D1/I2C3_SDA/DCMI_D3/TIM3_CH4_96") (pintype "passive"))
      (node (ref "ACT_mot34") (pin "5") (pinfunction "5_5") (pintype "passive"))
    )
    (net (code "32") (name "/ACT_PC10_Sens2") (class "Default")
      (node (ref "ACT_STM32F4DISCOVERY") (pin "87") (pinfunction "PC10/SPI3_SCK/I2S3_CK/UART4_TX/SDIO_D2/DCMI_D8/USART3_TX_87") (pintype "passive"))
      (node (ref "ACT__Mot12") (pin "6") (pinfunction "6_6") (pintype "passive"))
    )
    (net (code "33") (name "/ACT_PC11_Sens3") (class "Default")
      (node (ref "ACT_STM32F4DISCOVERY") (pin "88") (pinfunction "PC11/UART4_RX/SPI3_MISO/SDIO_D3/DCMI_D4/USART3_RX/I2S3ext_SD_88") (pintype "passive"))
      (node (ref "ACT_mot34") (pin "1") (pinfunction "1_1") (pintype "passive"))
    )
    (net (code "34") (name "/ACT_PC12_Sens4") (class "Default")
      (node (ref "ACT_STM32F4DISCOVERY") (pin "85") (pinfunction "PC12/UART5_TX/SDIO_CK/DCMI_D9/SPI3_MOSI/I2S3_SD/USART3_CK_85") (pintype "passive"))
      (node (ref "ACT_mot34") (pin "6") (pinfunction "6_6") (pintype "passive"))
    )
    (net (code "35") (name "/ACT_PC13_WHO_AM_I") (class "Default")
      (node (ref "ACT_RdwnWAmI") (pin "2") (pinfunction "2_2") (pintype "passive"))
      (node (ref "ACT_RupWAmI") (pin "1") (pinfunction "1_1") (pintype "passive"))
      (node (ref "ACT_STM32F4DISCOVERY") (pin "62") (pinfunction "PC13/RTC_AF1_62") (pintype "passive"))
    )
    (net (code "36") (name "/ACT_PD0_CANRX") (class "Default")
      (node (ref "ACT_STM32F4DISCOVERY") (pin "86") (pinfunction "PD0/FSMC_D2/CAN1_RX_86") (pintype "passive"))
      (node (ref "ACT_Ucan") (pin "4") (pinfunction "RXD_4") (pintype "output"))
    )
    (net (code "37") (name "/ACT_PD1_CANTX") (class "Default")
      (node (ref "ACT_STM32F4DISCOVERY") (pin "83") (pinfunction "PD1/FSMC_D3/CAN1_TX_83") (pintype "passive"))
      (node (ref "ACT_Ucan") (pin "1") (pinfunction "TXD_1") (pintype "input"))
    )
    (net (code "38") (name "/ACT_PD2_TOR1") (class "Default")
      (node (ref "ACT_STM32F4DISCOVERY") (pin "84") (pinfunction "PD2/TIM3_ETR/UART5_RXSDIO_CMD/DCMI_D11_84") (pintype "passive"))
      (node (ref "TOR") (pin "3") (pinfunction "3_3") (pintype "passive"))
    )
    (net (code "39") (name "/ACT_PD3_TOR2") (class "Default")
      (node (ref "ACT_STM32F4DISCOVERY") (pin "81") (pinfunction "PD3/FSMC_CLK/USART2_CTS_81") (pintype "passive"))
      (node (ref "TOR") (pin "2") (pinfunction "2_2") (pintype "passive"))
    )
    (net (code "40") (name "/ACT_PD6_RFU") (class "Default")
      (node (ref "ACT_RFU") (pin "3") (pinfunction "3_3") (pintype "passive"))
      (node (ref "ACT_STM32F4DISCOVERY") (pin "80") (pinfunction "PD6/FSMC_NWAIT/USART2_RX_80") (pintype "passive"))
    )
    (net (code "41") (name "/ACT_PD7_RFU") (class "Default")
      (node (ref "ACT_RFU") (pin "2") (pinfunction "2_2") (pintype "passive"))
      (node (ref "ACT_STM32F4DISCOVERY") (pin "77") (pinfunction "PD7/USART2_CK/FSMC_NE1/FSMC_NCE2_77") (pintype "passive"))
    )
    (net (code "42") (name "/ACT_PD8_MAX485_TX") (class "Default")
      (node (ref "ACT_MAX485") (pin "4") (pinfunction "DI_4") (pintype "input"))
      (node (ref "ACT_STM32F4DISCOVERY") (pin "40") (pinfunction "PD8/FSMC_D13/USART3_TX_40") (pintype "passive"))
    )
    (net (code "43") (name "/ACT_PD9_MAX485_RX") (class "Default")
      (node (ref "ACT_MAX485") (pin "1") (pinfunction "RO_1") (pintype "tri_state"))
      (node (ref "ACT_STM32F4DISCOVERY") (pin "41") (pinfunction "PD9/FSMC_D14/USART3_RX_41") (pintype "passive"))
    )
    (net (code "44") (name "/ACT_PD10_ERROR") (class "Default")
      (node (ref "ACT_Rderror") (pin "1") (pinfunction "1_1") (pintype "passive"))
      (node (ref "ACT_STM32F4DISCOVERY") (pin "42") (pinfunction "PD10/FSMC_D15/USART3_CK_42") (pintype "passive"))
    )
    (net (code "45") (name "/ACT_PD11_SELFTEST") (class "Default")
      (node (ref "ACT_Rdselftest") (pin "1") (pinfunction "1_1") (pintype "passive"))
      (node (ref "ACT_STM32F4DISCOVERY") (pin "43") (pinfunction "PD11/FSMC_A16/USART3_CTS_43") (pintype "passive"))
    )
    (net (code "46") (name "/ACT_PD12_RUN") (class "Default")
      (node (ref "ACT_STM32F4DISCOVERY") (pin "44") (pinfunction "PD12/FSMC_A17/TIM4_CH1/USART3_RTS_44") (pintype "passive"))
    )
    (net (code "47") (name "/ACT_PD13_CAN") (class "Default")
      (node (ref "ACT_STM32F4DISCOVERY") (pin "45") (pinfunction "PD13/FSMC_A18/TIM4_CH2_45") (pintype "passive"))
    )
    (net (code "48") (name "/ACT_PD14_UART") (class "Default")
      (node (ref "ACT_STM32F4DISCOVERY") (pin "46") (pinfunction "PD14/FSMC_D0/TIM4_CH3_46") (pintype "passive"))
    )
    (net (code "49") (name "/ACT_PD15_USER") (class "Default")
      (node (ref "ACT_STM32F4DISCOVERY") (pin "47") (pinfunction "PD15/FSMC_D1/TIM4_CH4_47") (pintype "passive"))
    )
    (net (code "50") (name "/ACT_PE5_Cod3A") (class "Default")
      (node (ref "ACT_Ccod3A") (pin "2") (pinfunction "2_2") (pintype "passive"))
      (node (ref "ACT_RCod3A") (pin "1") (pinfunction "1_1") (pintype "passive"))
      (node (ref "ACT_STM32F4DISCOVERY") (pin "64") (pinfunction "PE5/TRACED2/FSMC_A21/TIM9_CH1/DCMI_D6_64") (pintype "passive"))
    )
    (net (code "51") (name "/ACT_PE6_Cod3B") (class "Default")
      (node (ref "ACT_Ccod3B") (pin "2") (pinfunction "2_2") (pintype "passive"))
      (node (ref "ACT_RCod3B") (pin "1") (pinfunction "1_1") (pintype "passive"))
      (node (ref "ACT_STM32F4DISCOVERY") (pin "61") (pinfunction "PE6/TRACED3/FSMC_A22/TIM9_CH2/DCMI_D7_61") (pintype "passive"))
    )
    (net (code "52") (name "/ACT_PE8_I_AM_ACT") (class "Default")
      (node (ref "ACT_STM32F4DISCOVERY") (pin "26") (pinfunction "PE8/FSMC_D5/TIM1_CH1N_26") (pintype "passive"))
      (node (ref "st_i_am_a") (pin "2") (pinfunction "2_2") (pintype "passive"))
    )
    (net (code "53") (name "/ACT_PE10_MOSFET_7") (class "Default")
      (node (ref "ACT_8_MOSFET") (pin "2") (pinfunction "2_2") (pintype "passive"))
      (node (ref "ACT_STM32F4DISCOVERY") (pin "28") (pinfunction "PE10/FSMC_D7/TIM1_CH2N_28") (pintype "passive"))
      (node (ref "Servo0") (pin "3") (pinfunction "3_3") (pintype "passive"))
    )
    (net (code "54") (name "/ACT_PE11_servo") (class "Default")
      (node (ref "ACT_STM32F4DISCOVERY") (pin "29") (pinfunction "PE11/FSMC_D8/TIM1_CH2_29") (pintype "passive"))
      (node (ref "Servo1") (pin "3") (pinfunction "3_3") (pintype "passive"))
    )
    (net (code "55") (name "/ACT_PE12_servo") (class "Default")
      (node (ref "ACT_STM32F4DISCOVERY") (pin "30") (pinfunction "PE12/FSMC_D9/TIM1_CH3N_30") (pintype "passive"))
      (node (ref "Servo2") (pin "3") (pinfunction "3_3") (pintype "passive"))
    )
    (net (code "56") (name "/ACT_PE13_MOSFET_8") (class "Default")
      (node (ref "ACT_8_MOSFET") (pin "10") (pinfunction "10_10") (pintype "passive"))
      (node (ref "ACT_STM32F4DISCOVERY") (pin "31") (pinfunction "PE13/FSMC_D10/TIM1_CH3_31") (pintype "passive"))
      (node (ref "Servo3") (pin "3") (pinfunction "3_3") (pintype "passive"))
    )
    (net (code "57") (name "/ACT_PE14_servo") (class "Default")
      (node (ref "ACT_STM32F4DISCOVERY") (pin "32") (pinfunction "PE14/FSMC_D11/TIM1_CH4_32") (pintype "passive"))
      (node (ref "Servo4") (pin "3") (pinfunction "3_3") (pintype "passive"))
    )
    (net (code "58") (name "/ACT_PE15_servo") (class "Default")
      (node (ref "ACT_STM32F4DISCOVERY") (pin "33") (pinfunction "PE15/FSMC_D12/TIM1_BKIN_33") (pintype "passive"))
      (node (ref "Servo5") (pin "3") (pinfunction "3_3") (pintype "passive"))
    )
    (net (code "59") (name "/ACT_U1RX") (class "Default")
      (node (ref "ACT_Rsu1rx") (pin "2") (pinfunction "2_2") (pintype "passive"))
      (node (ref "ACT_UART1") (pin "4") (pinfunction "4_4") (pintype "passive"))
    )
    (net (code "60") (name "/ACT_U1TX") (class "Default")
      (node (ref "ACT_RpuU1tx") (pin "1") (pinfunction "1_1") (pintype "passive"))
      (node (ref "ACT_RsU1tx") (pin "1") (pinfunction "1_1") (pintype "passive"))
      (node (ref "ACT_UART1") (pin "3") (pinfunction "3_3") (pintype "passive"))
    )
    (net (code "61") (name "/CANH") (class "Default")
      (node (ref "ACT_Ucan") (pin "7") (pinfunction "CANH_7") (pintype "bidirectional"))
    )
    (net (code "62") (name "/CANL") (class "Default")
      (node (ref "ACT_Ucan") (pin "6") (pinfunction "CANL_6") (pintype "bidirectional"))
    )
    (net (code "63") (name "/MaxD") (class "Default")
      (node (ref "ACT_AX12_1") (pin "1") (pinfunction "1_1") (pintype "passive"))
      (node (ref "ACT_AX12_2") (pin "1") (pinfunction "1_1") (pintype "passive"))
      (node (ref "ACT_MAX485") (pin "6") (pinfunction "A_6") (pintype "bidirectional"))
      (node (ref "ACT_RpuMAX485") (pin "1") (pinfunction "1_1") (pintype "passive"))
    )
    (net (code "64") (name "/MaxD+") (class "Default")
      (node (ref "ACT_MAX485dif") (pin "6") (pinfunction "A_6") (pintype "bidirectional"))
      (node (ref "ACT_RX24") (pin "2") (pinfunction "2_2") (pintype "passive"))
      (node (ref "ACT_RX24_2") (pin "2") (pinfunction "2_2") (pintype "passive"))
      (node (ref "ACT_RpuMax485dif") (pin "1") (pinfunction "1_1") (pintype "passive"))
    )
    (net (code "65") (name "/MaxD-") (class "Default")
      (node (ref "ACT_MAX485dif") (pin "7") (pinfunction "~{B}_7") (pintype "bidirectional"))
      (node (ref "ACT_RX24") (pin "1") (pinfunction "1_1") (pintype "passive"))
      (node (ref "ACT_RX24_2") (pin "1") (pinfunction "1_1") (pintype "passive"))
    )
    (net (code "66") (name "3V_ACT") (class "Default")
      (node (ref "ACT_RpuAn11") (pin "2") (pinfunction "2_2") (pintype "passive"))
      (node (ref "ACT_RpuAn12") (pin "2") (pinfunction "2_2") (pintype "passive"))
      (node (ref "ACT_RpuAn13") (pin "2") (pinfunction "2_2") (pintype "passive"))
      (node (ref "ACT_RpuAn7") (pin "2") (pinfunction "2_2") (pintype "passive"))
      (node (ref "ACT_RpuAn8") (pin "2") (pinfunction "2_2") (pintype "passive"))
      (node (ref "ACT_RpuAn9") (pin "2") (pinfunction "2_2") (pintype "passive"))
      (node (ref "ACT_RpuU1rx") (pin "2") (pinfunction "2_2") (pintype "passive"))
      (node (ref "ACT_RpuU1tx") (pin "2") (pinfunction "2_2") (pintype "passive"))
      (node (ref "ACT_RupWAmI") (pin "2") (pinfunction "2_2") (pintype "passive"))
      (node (ref "ACT_STM32F4DISCOVERY") (pin "55") (pinfunction "3V_55") (pintype "passive"))
      (node (ref "ACT_STM32F4DISCOVERY") (pin "56") (pinfunction "3V_56") (pintype "passive"))
    )
    (net (code "67") (name "5V") (class "Default")
      (node (ref "ACT_8_MOSFET") (pin "1") (pinfunction "1_1") (pintype "passive"))
      (node (ref "ACT_AN11") (pin "4") (pinfunction "4_4") (pintype "passive"))
      (node (ref "ACT_AN12") (pin "4") (pinfunction "4_4") (pintype "passive"))
      (node (ref "ACT_AN13") (pin "4") (pinfunction "4_4") (pintype "passive"))
      (node (ref "ACT_AN7") (pin "4") (pinfunction "4_4") (pintype "passive"))
      (node (ref "ACT_AN9") (pin "4") (pinfunction "4_4") (pintype "passive"))
      (node (ref "ACT_CdCan1") (pin "2") (pinfunction "2_2") (pintype "passive"))
      (node (ref "ACT_CdCan2") (pin "2") (pinfunction "2_2") (pintype "passive"))
      (node (ref "ACT_CdMax485") (pin "2") (pinfunction "2_2") (pintype "passive"))
      (node (ref "ACT_CdMax485dif") (pin "2") (pinfunction "2_2") (pintype "passive"))
      (node (ref "ACT_MAX485") (pin "8") (pinfunction "VCC_8") (pintype "passive"))
      (node (ref "ACT_MAX485dif") (pin "8") (pinfunction "VCC_8") (pintype "passive"))
      (node (ref "ACT_Rmax485B+") (pin "2") (pinfunction "2_2") (pintype "passive"))
      (node (ref "ACT_RpuMAX485") (pin "2") (pinfunction "2_2") (pintype "passive"))
      (node (ref "ACT_RpuMax485dif") (pin "2") (pinfunction "2_2") (pintype "passive"))
      (node (ref "ACT_STM32F4DISCOVERY") (pin "53") (pinfunction "5V_53") (pintype "passive"))
      (node (ref "ACT_STM32F4DISCOVERY") (pin "54") (pinfunction "5V_54") (pintype "passive"))
      (node (ref "ACT_Ucan") (pin "3") (pinfunction "VDD_3") (pintype "power_in"))
      (node (ref "ACT_cod1") (pin "1") (pinfunction "1_1") (pintype "passive"))
      (node (ref "ACT_cod1") (pin "2") (pinfunction "2_2") (pintype "passive"))
      (node (ref "ACT_cod2") (pin "1") (pinfunction "1_1") (pintype "passive"))
      (node (ref "ACT_cod2") (pin "2") (pinfunction "2_2") (pintype "passive"))
      (node (ref "ACT_cod3") (pin "1") (pinfunction "1_1") (pintype "passive"))
      (node (ref "ACT_cod3") (pin "2") (pinfunction "2_2") (pintype "passive"))
      (node (ref "ACT_cod4") (pin "1") (pinfunction "1_1") (pintype "passive"))
      (node (ref "ACT_cod4") (pin "2") (pinfunction "2_2") (pintype "passive"))
    )
    (net (code "68") (name "5V_Perm") (class "Default")
      (node (ref "ACT_UART1") (pin "1") (pinfunction "1_1") (pintype "passive"))
      (node (ref "ACT_UART1") (pin "2") (pinfunction "2_2") (pintype "passive"))
    )
    (net (code "69") (name "5V_servos") (class "Default")
      (node (ref "Servo0") (pin "2") (pinfunction "2_2") (pintype "passive"))
      (node (ref "Servo1") (pin "2") (pinfunction "2_2") (pintype "passive"))
      (node (ref "Servo2") (pin "2") (pinfunction "2_2") (pintype "passive"))
      (node (ref "Servo3") (pin "2") (pinfunction "2_2") (pintype "passive"))
      (node (ref "Servo4") (pin "2") (pinfunction "2_2") (pintype "passive"))
      (node (ref "Servo5") (pin "2") (pinfunction "2_2") (pintype "passive"))
    )
    (net (code "70") (name "12V") (class "Default")
      (node (ref "ACT_AX12_1") (pin "2") (pinfunction "2_2") (pintype "passive"))
      (node (ref "ACT_AX12_2") (pin "2") (pinfunction "2_2") (pintype "passive"))
      (node (ref "ACT_RX24") (pin "3") (pinfunction "3_3") (pintype "passive"))
      (node (ref "ACT_RX24_2") (pin "3") (pinfunction "3_3") (pintype "passive"))
    )
    (net (code "71") (name "24V") (class "Default")
      (node (ref "ACT_AN11") (pin "3") (pinfunction "3_3") (pintype "passive"))
      (node (ref "ACT_AN12") (pin "3") (pinfunction "3_3") (pintype "passive"))
      (node (ref "ACT_AN13") (pin "3") (pinfunction "3_3") (pintype "passive"))
      (node (ref "ACT_AN7") (pin "3") (pinfunction "3_3") (pintype "passive"))
      (node (ref "ACT_AN8") (pin "3") (pinfunction "3_3") (pintype "passive"))
      (node (ref "ACT_AN9") (pin "3") (pinfunction "3_3") (pintype "passive"))
      (node (ref "ACT_CdAN11") (pin "2") (pinfunction "2_2") (pintype "passive"))
      (node (ref "ACT_CdAN12") (pin "2") (pinfunction "2_2") (pintype "passive"))
      (node (ref "ACT_CdAN13") (pin "2") (pinfunction "2_2") (pintype "passive"))
      (node (ref "ACT_CdAN7") (pin "2") (pinfunction "2_2") (pintype "passive"))
      (node (ref "ACT_CdAN8") (pin "2") (pinfunction "2_2") (pintype "passive"))
      (node (ref "ACT_CdAN9") (pin "2") (pinfunction "2_2") (pintype "passive"))
    )
    (net (code "72") (name "GND") (class "Default")
      (node (ref "ACT_8_MOSFET") (pin "9") (pinfunction "9_9") (pintype "passive"))
      (node (ref "ACT_Ccod1A") (pin "1") (pinfunction "1_1") (pintype "passive"))
      (node (ref "ACT_Ccod1B") (pin "1") (pinfunction "1_1") (pintype "passive"))
      (node (ref "ACT_Ccod2A") (pin "1") (pinfunction "1_1") (pintype "passive"))
      (node (ref "ACT_Ccod2B") (pin "1") (pinfunction "1_1") (pintype "passive"))
      (node (ref "ACT_Ccod3A") (pin "1") (pinfunction "1_1") (pintype "passive"))
      (node (ref "ACT_Ccod3B") (pin "1") (pinfunction "1_1") (pintype "passive"))
      (node (ref "ACT_Ccod4A") (pin "1") (pinfunction "1_1") (pintype "passive"))
      (node (ref "ACT_Ccod4B") (pin "1") (pinfunction "1_1") (pintype "passive"))
      (node (ref "ACT_CdCan1") (pin "1") (pinfunction "1_1") (pintype "passive"))
      (node (ref "ACT_CdCan2") (pin "1") (pinfunction "1_1") (pintype "passive"))
      (node (ref "ACT_CdMax485") (pin "1") (pinfunction "1_1") (pintype "passive"))
      (node (ref "ACT_CdMax485dif") (pin "1") (pinfunction "1_1") (pintype "passive"))
      (node (ref "ACT_CfAn11") (pin "1") (pinfunction "1_1") (pintype "passive"))
      (node (ref "ACT_CfAn12") (pin "1") (pinfunction "1_1") (pintype "passive"))
      (node (ref "ACT_CfAn13") (pin "1") (pinfunction "1_1") (pintype "passive"))
      (node (ref "ACT_CfAn14") (pin "1") (pinfunction "1_1") (pintype "passive"))
      (node (ref "ACT_CfAn15") (pin "1") (pinfunction "1_1") (pintype "passive"))
      (node (ref "ACT_CfAn7") (pin "1") (pinfunction "1_1") (pintype "passive"))
      (node (ref "ACT_CfAn8") (pin "1") (pinfunction "1_1") (pintype "passive"))
      (node (ref "ACT_CfAn9") (pin "1") (pinfunction "1_1") (pintype "passive"))
      (node (ref "ACT_Cu1rx") (pin "1") (pinfunction "1_1") (pintype "passive"))
      (node (ref "ACT_DSelftest") (pin "2") (pinfunction "K_2") (pintype "passive"))
      (node (ref "ACT_Derror") (pin "2") (pinfunction "K_2") (pintype "passive"))
      (node (ref "ACT_MAX485") (pin "5") (pinfunction "GND_5") (pintype "passive"))
      (node (ref "ACT_MAX485dif") (pin "5") (pinfunction "GND_5") (pintype "passive"))
      (node (ref "ACT_RFU") (pin "1") (pinfunction "1_1") (pintype "passive"))
      (node (ref "ACT_RdwnAn11") (pin "1") (pinfunction "1_1") (pintype "passive"))
      (node (ref "ACT_RdwnAn12") (pin "1") (pinfunction "1_1") (pintype "passive"))
      (node (ref "ACT_RdwnAn13") (pin "1") (pinfunction "1_1") (pintype "passive"))
      (node (ref "ACT_RdwnAn7") (pin "1") (pinfunction "1_1") (pintype "passive"))
      (node (ref "ACT_RdwnAn8") (pin "1") (pinfunction "1_1") (pintype "passive"))
      (node (ref "ACT_RdwnAn9") (pin "1") (pinfunction "1_1") (pintype "passive"))
      (node (ref "ACT_RdwnWAmI") (pin "1") (pinfunction "1_1") (pintype "passive"))
      (node (ref "ACT_Rmax485B-") (pin "1") (pinfunction "1_1") (pintype "passive"))
      (node (ref "ACT_STM32F4DISCOVERY") (pin "1") (pinfunction "GND_1") (pintype "passive"))
      (node (ref "ACT_STM32F4DISCOVERY") (pin "100") (pinfunction "GND_100") (pintype "passive"))
      (node (ref "ACT_STM32F4DISCOVERY") (pin "2") (pinfunction "GND_2") (pintype "passive"))
      (node (ref "ACT_STM32F4DISCOVERY") (pin "23") (pinfunction "GND_23") (pintype "passive"))
      (node (ref "ACT_STM32F4DISCOVERY") (pin "49") (pinfunction "GND_49") (pintype "passive"))
      (node (ref "ACT_STM32F4DISCOVERY") (pin "5") (pinfunction "GND_5") (pintype "passive"))
      (node (ref "ACT_STM32F4DISCOVERY") (pin "50") (pinfunction "GND_50") (pintype "passive"))
      (node (ref "ACT_STM32F4DISCOVERY") (pin "51") (pinfunction "GND_51") (pintype "passive"))
      (node (ref "ACT_STM32F4DISCOVERY") (pin "52") (pinfunction "GND_52") (pintype "passive"))
      (node (ref "ACT_STM32F4DISCOVERY") (pin "99") (pinfunction "GND_99") (pintype "passive"))
      (node (ref "ACT_UART1") (pin "5") (pinfunction "5_5") (pintype "passive"))
      (node (ref "ACT_UART1") (pin "6") (pinfunction "6_6") (pintype "passive"))
      (node (ref "ACT_Ucan") (pin "2") (pinfunction "VSS_2") (pintype "power_in"))
      (node (ref "ACT_Ucan") (pin "8") (pinfunction "RS_8") (pintype "input"))
      (node (ref "ACT__Mot12") (pin "3") (pinfunction "3_3") (pintype "passive"))
      (node (ref "ACT__Mot12") (pin "4") (pinfunction "4_4") (pintype "passive"))
      (node (ref "ACT_cod1") (pin "5") (pinfunction "5_5") (pintype "passive"))
      (node (ref "ACT_cod1") (pin "6") (pinfunction "6_6") (pintype "passive"))
      (node (ref "ACT_cod2") (pin "5") (pinfunction "5_5") (pintype "passive"))
      (node (ref "ACT_cod2") (pin "6") (pinfunction "6_6") (pintype "passive"))
      (node (ref "ACT_cod3") (pin "5") (pinfunction "5_5") (pintype "passive"))
      (node (ref "ACT_cod3") (pin "6") (pinfunction "6_6") (pintype "passive"))
      (node (ref "ACT_cod4") (pin "5") (pinfunction "5_5") (pintype "passive"))
      (node (ref "ACT_cod4") (pin "6") (pinfunction "6_6") (pintype "passive"))
      (node (ref "ACT_currentMot") (pin "1") (pinfunction "1_1") (pintype "passive"))
      (node (ref "ACT_mot34") (pin "3") (pinfunction "3_3") (pintype "passive"))
      (node (ref "ACT_mot34") (pin "4") (pinfunction "4_4") (pintype "passive"))
      (node (ref "ACT_stAN11") (pin "3") (pinfunction "3_3") (pintype "passive"))
      (node (ref "ACT_stAN12") (pin "3") (pinfunction "3_3") (pintype "passive"))
      (node (ref "ACT_stAN13") (pin "3") (pinfunction "3_3") (pintype "passive"))
      (node (ref "ACT_stAN7") (pin "3") (pinfunction "3_3") (pintype "passive"))
      (node (ref "ACT_stAN9") (pin "3") (pinfunction "3_3") (pintype "passive"))
      (node (ref "TOR") (pin "1") (pinfunction "1_1") (pintype "passive"))
      (node (ref "st_i_am_a") (pin "1") (pinfunction "1_1") (pintype "passive"))
    )
    (net (code "73") (name "GND_5") (class "Default")
      (node (ref "Servo0") (pin "1") (pinfunction "1_1") (pintype "passive"))
      (node (ref "Servo1") (pin "1") (pinfunction "1_1") (pintype "passive"))
      (node (ref "Servo2") (pin "1") (pinfunction "1_1") (pintype "passive"))
      (node (ref "Servo3") (pin "1") (pinfunction "1_1") (pintype "passive"))
      (node (ref "Servo4") (pin "1") (pinfunction "1_1") (pintype "passive"))
      (node (ref "Servo5") (pin "1") (pinfunction "1_1") (pintype "passive"))
    )
    (net (code "74") (name "GND_12") (class "Default")
      (node (ref "ACT_AX12_1") (pin "3") (pinfunction "3_3") (pintype "passive"))
      (node (ref "ACT_AX12_2") (pin "3") (pinfunction "3_3") (pintype "passive"))
      (node (ref "ACT_RX24") (pin "4") (pinfunction "4_4") (pintype "passive"))
      (node (ref "ACT_RX24_2") (pin "4") (pinfunction "4_4") (pintype "passive"))
    )
    (net (code "75") (name "GND_24") (class "Default")
      (node (ref "ACT_AN8") (pin "1") (pinfunction "1_1") (pintype "passive"))
      (node (ref "ACT_CdAN11") (pin "1") (pinfunction "1_1") (pintype "passive"))
      (node (ref "ACT_CdAN12") (pin "1") (pinfunction "1_1") (pintype "passive"))
      (node (ref "ACT_CdAN13") (pin "1") (pinfunction "1_1") (pintype "passive"))
      (node (ref "ACT_CdAN7") (pin "1") (pinfunction "1_1") (pintype "passive"))
      (node (ref "ACT_CdAN8") (pin "1") (pinfunction "1_1") (pintype "passive"))
      (node (ref "ACT_CdAN9") (pin "1") (pinfunction "1_1") (pintype "passive"))
      (node (ref "ACT_stAN11") (pin "1") (pinfunction "1_1") (pintype "passive"))
      (node (ref "ACT_stAN12") (pin "1") (pinfunction "1_1") (pintype "passive"))
      (node (ref "ACT_stAN13") (pin "1") (pinfunction "1_1") (pintype "passive"))
      (node (ref "ACT_stAN7") (pin "1") (pinfunction "1_1") (pintype "passive"))
      (node (ref "ACT_stAN9") (pin "1") (pinfunction "1_1") (pintype "passive"))
    )
    (net (code "76") (name "Net-(ACT_AN7-Pad1)") (class "Default")
      (node (ref "ACT_AN7") (pin "1") (pinfunction "1_1") (pintype "passive"))
      (node (ref "ACT_stAN7") (pin "2") (pinfunction "2_2") (pintype "passive"))
    )
    (net (code "77") (name "Net-(ACT_AN7-Pad2)") (class "Default")
      (node (ref "ACT_AN7") (pin "2") (pinfunction "2_2") (pintype "passive"))
      (node (ref "ACT_RdwnAn7") (pin "2") (pinfunction "2_2") (pintype "passive"))
      (node (ref "ACT_RfAn7") (pin "2") (pinfunction "2_2") (pintype "passive"))
    )
    (net (code "78") (name "Net-(ACT_AN8-Pad2)") (class "Default")
      (node (ref "ACT_AN8") (pin "2") (pinfunction "2_2") (pintype "passive"))
      (node (ref "ACT_RdwnAn8") (pin "2") (pinfunction "2_2") (pintype "passive"))
      (node (ref "ACT_RfAn8") (pin "2") (pinfunction "2_2") (pintype "passive"))
    )
    (net (code "79") (name "Net-(ACT_AN9-Pad1)") (class "Default")
      (node (ref "ACT_AN9") (pin "1") (pinfunction "1_1") (pintype "passive"))
      (node (ref "ACT_stAN9") (pin "2") (pinfunction "2_2") (pintype "passive"))
    )
    (net (code "80") (name "Net-(ACT_AN9-Pad2)") (class "Default")
      (node (ref "ACT_AN9") (pin "2") (pinfunction "2_2") (pintype "passive"))
      (node (ref "ACT_RdwnAn9") (pin "2") (pinfunction "2_2") (pintype "passive"))
      (node (ref "ACT_RfAn9") (pin "2") (pinfunction "2_2") (pintype "passive"))
    )
    (net (code "81") (name "Net-(ACT_AN11-Pad1)") (class "Default")
      (node (ref "ACT_AN11") (pin "1") (pinfunction "1_1") (pintype "passive"))
      (node (ref "ACT_stAN11") (pin "2") (pinfunction "2_2") (pintype "passive"))
    )
    (net (code "82") (name "Net-(ACT_AN11-Pad2)") (class "Default")
      (node (ref "ACT_AN11") (pin "2") (pinfunction "2_2") (pintype "passive"))
      (node (ref "ACT_RdwnAn11") (pin "2") (pinfunction "2_2") (pintype "passive"))
      (node (ref "ACT_RfAn11") (pin "2") (pinfunction "2_2") (pintype "passive"))
    )
    (net (code "83") (name "Net-(ACT_AN12-Pad1)") (class "Default")
      (node (ref "ACT_AN12") (pin "1") (pinfunction "1_1") (pintype "passive"))
      (node (ref "ACT_stAN12") (pin "2") (pinfunction "2_2") (pintype "passive"))
    )
    (net (code "84") (name "Net-(ACT_AN12-Pad2)") (class "Default")
      (node (ref "ACT_AN12") (pin "2") (pinfunction "2_2") (pintype "passive"))
      (node (ref "ACT_RdwnAn12") (pin "2") (pinfunction "2_2") (pintype "passive"))
      (node (ref "ACT_RfAn12") (pin "2") (pinfunction "2_2") (pintype "passive"))
    )
    (net (code "85") (name "Net-(ACT_AN13-Pad1)") (class "Default")
      (node (ref "ACT_AN13") (pin "1") (pinfunction "1_1") (pintype "passive"))
      (node (ref "ACT_stAN13") (pin "2") (pinfunction "2_2") (pintype "passive"))
    )
    (net (code "86") (name "Net-(ACT_AN13-Pad2)") (class "Default")
      (node (ref "ACT_AN13") (pin "2") (pinfunction "2_2") (pintype "passive"))
      (node (ref "ACT_RdwnAn13") (pin "2") (pinfunction "2_2") (pintype "passive"))
      (node (ref "ACT_RfAn13") (pin "2") (pinfunction "2_2") (pintype "passive"))
    )
    (net (code "87") (name "Net-(ACT_DSelftest-A)") (class "Default")
      (node (ref "ACT_DSelftest") (pin "1") (pinfunction "A_1") (pintype "passive"))
      (node (ref "ACT_Rdselftest") (pin "2") (pinfunction "2_2") (pintype "passive"))
    )
    (net (code "88") (name "Net-(ACT_Derror-A)") (class "Default")
      (node (ref "ACT_Derror") (pin "1") (pinfunction "A_1") (pintype "passive"))
      (node (ref "ACT_Rderror") (pin "2") (pinfunction "2_2") (pintype "passive"))
    )
    (net (code "89") (name "Net-(ACT_MAX485-~{B})") (class "Default")
      (node (ref "ACT_MAX485") (pin "7") (pinfunction "~{B}_7") (pintype "bidirectional"))
      (node (ref "ACT_Rmax485B+") (pin "1") (pinfunction "1_1") (pintype "passive"))
      (node (ref "ACT_Rmax485B-") (pin "2") (pinfunction "2_2") (pintype "passive"))
    )
    (net (code "90") (name "Net-(ACT_RCod1A-Pad2)") (class "Default")
      (node (ref "ACT_RCod1A") (pin "2") (pinfunction "2_2") (pintype "passive"))
      (node (ref "ACT_cod1") (pin "3") (pinfunction "3_3") (pintype "passive"))
    )
    (net (code "91") (name "Net-(ACT_RCod1B-Pad2)") (class "Default")
      (node (ref "ACT_RCod1B") (pin "2") (pinfunction "2_2") (pintype "passive"))
      (node (ref "ACT_cod1") (pin "4") (pinfunction "4_4") (pintype "passive"))
    )
    (net (code "92") (name "Net-(ACT_RCod2A-Pad2)") (class "Default")
      (node (ref "ACT_RCod2A") (pin "2") (pinfunction "2_2") (pintype "passive"))
      (node (ref "ACT_cod2") (pin "3") (pinfunction "3_3") (pintype "passive"))
    )
    (net (code "93") (name "Net-(ACT_RCod2B-Pad2)") (class "Default")
      (node (ref "ACT_RCod2B") (pin "2") (pinfunction "2_2") (pintype "passive"))
      (node (ref "ACT_cod2") (pin "4") (pinfunction "4_4") (pintype "passive"))
    )
    (net (code "94") (name "Net-(ACT_RCod3A-Pad2)") (class "Default")
      (node (ref "ACT_RCod3A") (pin "2") (pinfunction "2_2") (pintype "passive"))
      (node (ref "ACT_cod3") (pin "3") (pinfunction "3_3") (pintype "passive"))
    )
    (net (code "95") (name "Net-(ACT_RCod3B-Pad2)") (class "Default")
      (node (ref "ACT_RCod3B") (pin "2") (pinfunction "2_2") (pintype "passive"))
      (node (ref "ACT_cod3") (pin "4") (pinfunction "4_4") (pintype "passive"))
    )
    (net (code "96") (name "Net-(ACT_RCod4A-Pad2)") (class "Default")
      (node (ref "ACT_RCod4A") (pin "2") (pinfunction "2_2") (pintype "passive"))
      (node (ref "ACT_cod4") (pin "3") (pinfunction "3_3") (pintype "passive"))
    )
    (net (code "97") (name "Net-(ACT_RCod4B-Pad2)") (class "Default")
      (node (ref "ACT_RCod4B") (pin "2") (pinfunction "2_2") (pintype "passive"))
      (node (ref "ACT_cod4") (pin "4") (pinfunction "4_4") (pintype "passive"))
    )
    (net (code "98") (name "Net-(ACT_RfAn14-Pad2)") (class "Default")
      (node (ref "ACT_RfAn14") (pin "2") (pinfunction "2_2") (pintype "passive"))
      (node (ref "ACT_currentMot") (pin "3") (pinfunction "3_3") (pintype "passive"))
    )
    (net (code "99") (name "Net-(ACT_RfAn15-Pad2)") (class "Default")
      (node (ref "ACT_RfAn15") (pin "2") (pinfunction "2_2") (pintype "passive"))
      (node (ref "ACT_currentMot") (pin "2") (pinfunction "2_2") (pintype "passive"))
    )
    (net (code "100") (name "unconnected-(ACT_RFU-Pad4)") (class "Default")
      (node (ref "ACT_RFU") (pin "4") (pinfunction "4_4") (pintype "passive"))
    )
    (net (code "101") (name "unconnected-(ACT_STM32F4DISCOVERY-BOOT0{slash}VPP-Pad71)") (class "Default")
      (node (ref "ACT_STM32F4DISCOVERY") (pin "71") (pinfunction "BOOT0/VPP_71") (pintype "passive+no_connect"))
    )
    (net (code "102") (name "unconnected-(ACT_STM32F4DISCOVERY-NC-Pad48)") (class "Default")
      (node (ref "ACT_STM32F4DISCOVERY") (pin "48") (pinfunction "NC_48") (pintype "passive+no_connect"))
    )
    (net (code "103") (name "unconnected-(ACT_STM32F4DISCOVERY-NRST-Pad6)") (class "Default")
      (node (ref "ACT_STM32F4DISCOVERY") (pin "6") (pinfunction "NRST_6") (pintype "passive+no_connect"))
    )
    (net (code "104") (name "unconnected-(ACT_STM32F4DISCOVERY-PA0-WKUP{slash}USART2_CTS{slash}USART4_TX{slash}ETH_MII_CRS{slash}TIM2_CH1_ETR{slash}TIM5_CH1{slash}TIM8_ETR{slash}ADC123_IN0{slash}WKUP-Pad12)") (class "Default")
      (node (ref "ACT_STM32F4DISCOVERY") (pin "12") (pinfunction "PA0-WKUP/USART2_CTS/USART4_TX/ETH_MII_CRS/TIM2_CH1_ETR/TIM5_CH1/TIM8_ETR/ADC123_IN0/WKUP_12") (pintype "passive+no_connect"))
    )
    (net (code "105") (name "unconnected-(ACT_STM32F4DISCOVERY-PA4{slash}SPI1_NSS{slash}SPI3_NSS{slash}USART2_CK{slash}DCMI_HSYNC{slash}OTG_HS_SOF{slash}I2S3_WS{slash}ADC12_IN4{slash}DAC1_OUT-Pad16)") (class "Default")
      (node (ref "ACT_STM32F4DISCOVERY") (pin "16") (pinfunction "PA4/SPI1_NSS/SPI3_NSS/USART2_CK/DCMI_HSYNC/OTG_HS_SOF/I2S3_WS/ADC12_IN4/DAC1_OUT_16") (pintype "passive+no_connect"))
    )
    (net (code "106") (name "unconnected-(ACT_STM32F4DISCOVERY-PA6{slash}SPI1_MISO{slash}TIM8_BKIN{slash}TIM13_CH1{slash}DCMI_PIXCLK{slash}TIM3_CH1{slash}TIM1_BKIN{slash}ADC12_IN6-Pad18)") (class "Default")
      (node (ref "ACT_STM32F4DISCOVERY") (pin "18") (pinfunction "PA6/SPI1_MISO/TIM8_BKIN/TIM13_CH1/DCMI_PIXCLK/TIM3_CH1/TIM1_BKIN/ADC12_IN6_18") (pintype "passive+no_connect"))
    )
    (net (code "107") (name "unconnected-(ACT_STM32F4DISCOVERY-PA9{slash}USART1_TX{slash}TIM1_CH2{slash}I2C3_SMBA{slash}DCMI_D0{slash}OTG_FS_VBUS-Pad94)") (class "Default")
      (node (ref "ACT_STM32F4DISCOVERY") (pin "94") (pinfunction "PA9/USART1_TX/TIM1_CH2/I2C3_SMBA/DCMI_D0/OTG_FS_VBUS_94") (pintype "passive+no_connect"))
    )
    (net (code "108") (name "unconnected-(ACT_STM32F4DISCOVERY-PA10{slash}USART1_RX{slash}TIM1_CH3{slash}OTG_FS_ID{slash}DCMI_D1-Pad91)") (class "Default")
      (node (ref "ACT_STM32F4DISCOVERY") (pin "91") (pinfunction "PA10/USART1_RX/TIM1_CH3/OTG_FS_ID/DCMI_D1_91") (pintype "passive+no_connect"))
    )
    (net (code "109") (name "unconnected-(ACT_STM32F4DISCOVERY-PA13{slash}JTMS_SWDIO-Pad92)") (class "Default")
      (node (ref "ACT_STM32F4DISCOVERY") (pin "92") (pinfunction "PA13/JTMS_SWDIO_92") (pintype "passive+no_connect"))
    )
    (net (code "110") (name "unconnected-(ACT_STM32F4DISCOVERY-PA14{slash}JTCK_SWCLK-Pad89)") (class "Default")
      (node (ref "ACT_STM32F4DISCOVERY") (pin "89") (pinfunction "PA14/JTCK_SWCLK_89") (pintype "passive+no_connect"))
    )
    (net (code "111") (name "unconnected-(ACT_STM32F4DISCOVERY-PB3{slash}JTDO{slash}TRACESWO{slash}SPI3_SCK{slash}I2S3_CK{slash}TIM2_CH2{slash}SPI1_SCK-Pad78)") (class "Default")
      (node (ref "ACT_STM32F4DISCOVERY") (pin "78") (pinfunction "PB3/JTDO/TRACESWO/SPI3_SCK/I2S3_CK/TIM2_CH2/SPI1_SCK_78") (pintype "passive+no_connect"))
    )
    (net (code "112") (name "unconnected-(ACT_STM32F4DISCOVERY-PC0{slash}OTG_HS_ULPI_STP{slash}ADC123_IN10-Pad8)") (class "Default")
      (node (ref "ACT_STM32F4DISCOVERY") (pin "8") (pinfunction "PC0/OTG_HS_ULPI_STP/ADC123_IN10_8") (pintype "passive+no_connect"))
    )
    (net (code "113") (name "unconnected-(ACT_STM32F4DISCOVERY-PC14{slash}OSC32_IN-Pad59)") (class "Default")
      (node (ref "ACT_STM32F4DISCOVERY") (pin "59") (pinfunction "PC14/OSC32_IN_59") (pintype "passive+no_connect"))
    )
    (net (code "114") (name "unconnected-(ACT_STM32F4DISCOVERY-PC15{slash}OSC32_OUT-Pad60)") (class "Default")
      (node (ref "ACT_STM32F4DISCOVERY") (pin "60") (pinfunction "PC15/OSC32_OUT_60") (pintype "passive+no_connect"))
    )
    (net (code "115") (name "unconnected-(ACT_STM32F4DISCOVERY-PD4{slash}FSMC_NOE{slash}USART2_RTS-Pad82)") (class "Default")
      (node (ref "ACT_STM32F4DISCOVERY") (pin "82") (pinfunction "PD4/FSMC_NOE/USART2_RTS_82") (pintype "passive+no_connect"))
    )
    (net (code "116") (name "unconnected-(ACT_STM32F4DISCOVERY-PD5{slash}FSMC_NWE{slash}USART2_TX-Pad79)") (class "Default")
      (node (ref "ACT_STM32F4DISCOVERY") (pin "79") (pinfunction "PD5/FSMC_NWE/USART2_TX_79") (pintype "passive+no_connect"))
    )
    (net (code "117") (name "unconnected-(ACT_STM32F4DISCOVERY-PE0{slash}TIM4_ETR{slash}FSMC_NBL0{slash}DCMI_D2-Pad67)") (class "Default")
      (node (ref "ACT_STM32F4DISCOVERY") (pin "67") (pinfunction "PE0/TIM4_ETR/FSMC_NBL0/DCMI_D2_67") (pintype "passive+no_connect"))
    )
    (net (code "118") (name "unconnected-(ACT_STM32F4DISCOVERY-PE1{slash}FSMC_NBL1{slash}DCMI_D3-Pad68)") (class "Default")
      (node (ref "ACT_STM32F4DISCOVERY") (pin "68") (pinfunction "PE1/FSMC_NBL1/DCMI_D3_68") (pintype "passive+no_connect"))
    )
    (net (code "119") (name "unconnected-(ACT_STM32F4DISCOVERY-PE2{slash}TRACECLK{slash}FSMC_A23{slash}ETH_MII_TXD3-Pad65)") (class "Default")
      (node (ref "ACT_STM32F4DISCOVERY") (pin "65") (pinfunction "PE2/TRACECLK/FSMC_A23/ETH_MII_TXD3_65") (pintype "passive+no_connect"))
    )
    (net (code "120") (name "unconnected-(ACT_STM32F4DISCOVERY-PE3{slash}TRACED0{slash}FSMC_A19-Pad66)") (class "Default")
      (node (ref "ACT_STM32F4DISCOVERY") (pin "66") (pinfunction "PE3/TRACED0/FSMC_A19_66") (pintype "passive+no_connect"))
    )
    (net (code "121") (name "unconnected-(ACT_STM32F4DISCOVERY-PE4{slash}TRACED1{slash}FSMC_A20{slash}DCMI_D4-Pad63)") (class "Default")
      (node (ref "ACT_STM32F4DISCOVERY") (pin "63") (pinfunction "PE4/TRACED1/FSMC_A20/DCMI_D4_63") (pintype "passive+no_connect"))
    )
    (net (code "122") (name "unconnected-(ACT_STM32F4DISCOVERY-PE7{slash}FSMC_D4{slash}TIM1_ETR-Pad25)") (class "Default")
      (node (ref "ACT_STM32F4DISCOVERY") (pin "25") (pinfunction "PE7/FSMC_D4/TIM1_ETR_25") (pintype "passive+no_connect"))
    )
    (net (code "123") (name "unconnected-(ACT_STM32F4DISCOVERY-PE9{slash}FSMC_D6{slash}TIM1_CH1-Pad27)") (class "Default")
      (node (ref "ACT_STM32F4DISCOVERY") (pin "27") (pinfunction "PE9/FSMC_D6/TIM1_CH1_27") (pintype "passive+no_connect"))
    )
    (net (code "124") (name "unconnected-(ACT_STM32F4DISCOVERY-PH0{slash}OSC_IN-Pad57)") (class "Default")
      (node (ref "ACT_STM32F4DISCOVERY") (pin "57") (pinfunction "PH0/OSC_IN_57") (pintype "passive+no_connect"))
    )
    (net (code "125") (name "unconnected-(ACT_STM32F4DISCOVERY-PH1{slash}OSC_OUT-Pad58)") (class "Default")
      (node (ref "ACT_STM32F4DISCOVERY") (pin "58") (pinfunction "PH1/OSC_OUT_58") (pintype "passive+no_connect"))
    )
    (net (code "126") (name "unconnected-(ACT_STM32F4DISCOVERY-VDD-Pad3)") (class "Default")
      (node (ref "ACT_STM32F4DISCOVERY") (pin "3") (pinfunction "VDD_3") (pintype "passive+no_connect"))
    )
    (net (code "127") (name "unconnected-(ACT_STM32F4DISCOVERY-VDD-Pad4)") (class "Default")
      (node (ref "ACT_STM32F4DISCOVERY") (pin "4") (pinfunction "VDD_4") (pintype "passive+no_connect"))
    )
    (net (code "128") (name "unconnected-(ACT_STM32F4DISCOVERY-VDD-Pad72)") (class "Default")
      (node (ref "ACT_STM32F4DISCOVERY") (pin "72") (pinfunction "VDD_72") (pintype "passive+no_connect"))
    )
    (net (code "129") (name "unconnected-(ACT_Ucan-VREF-Pad5)") (class "Default")
      (node (ref "ACT_Ucan") (pin "5") (pinfunction "VREF_5") (pintype "output"))
    )
  )
)
